# io-board-c-1.net
KiCad netlist of a schematic drawn in EAGLE
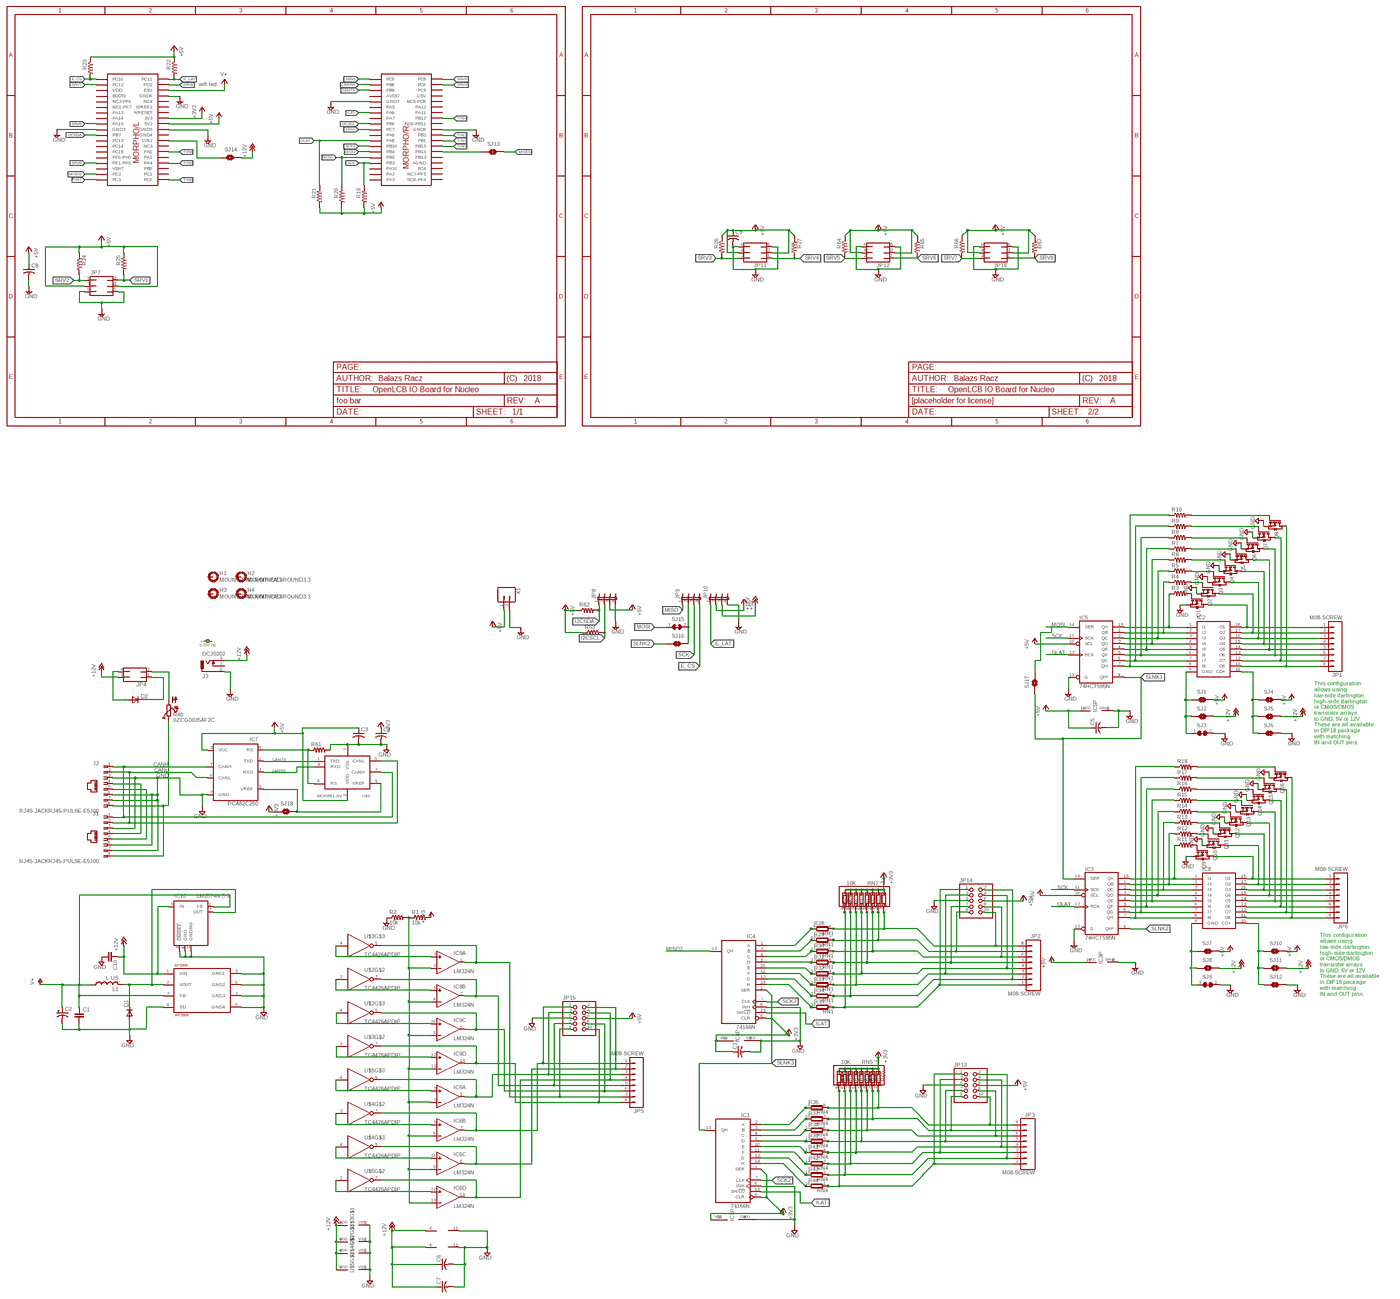
[diagram p0: schematic, sheet 1, overview]
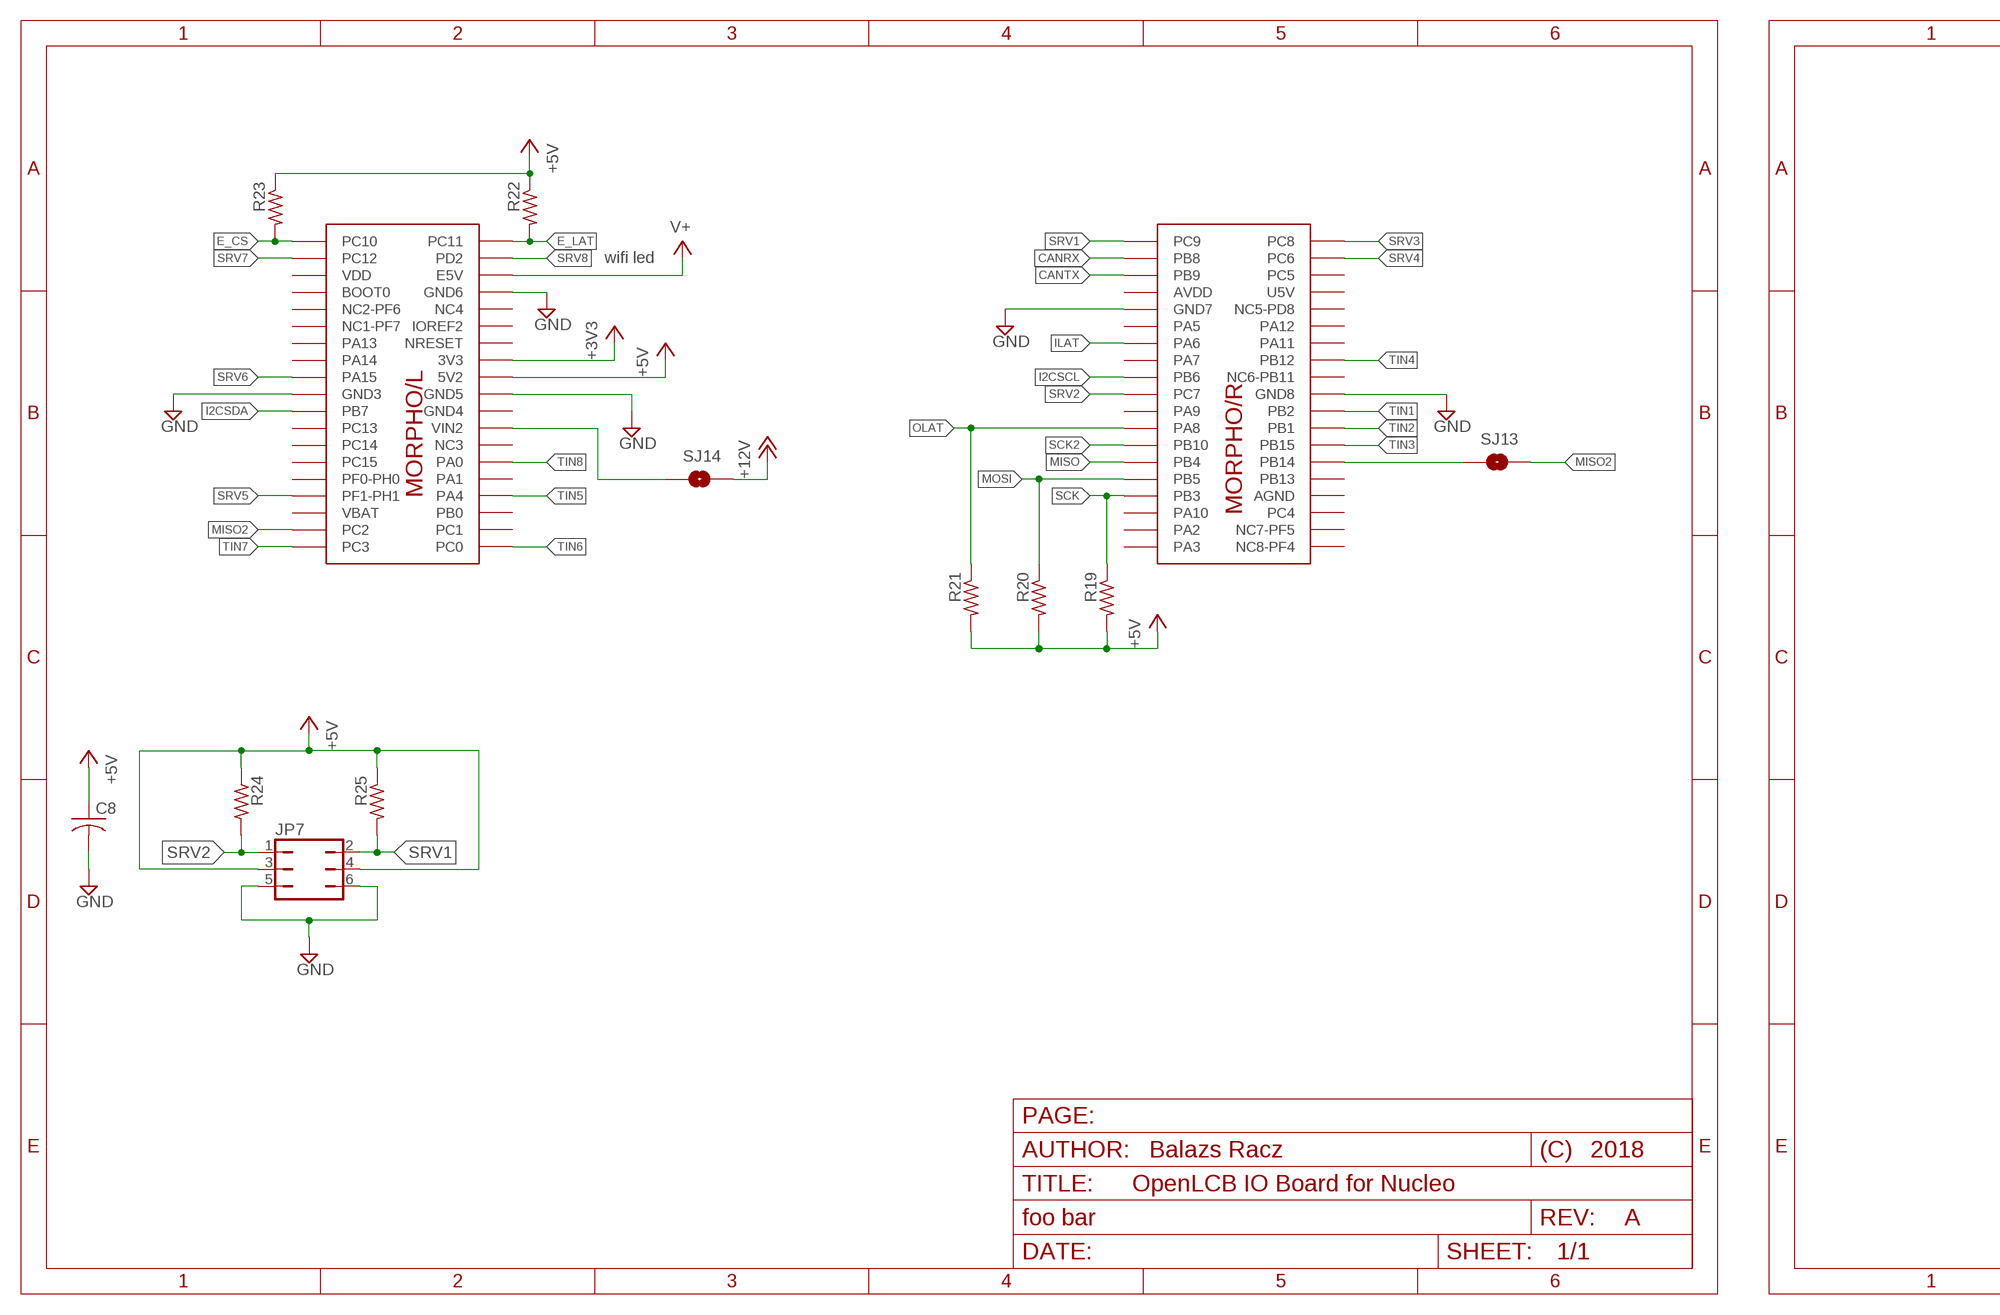
[diagram p1: schematic, sheet 1, part 1 of 4]
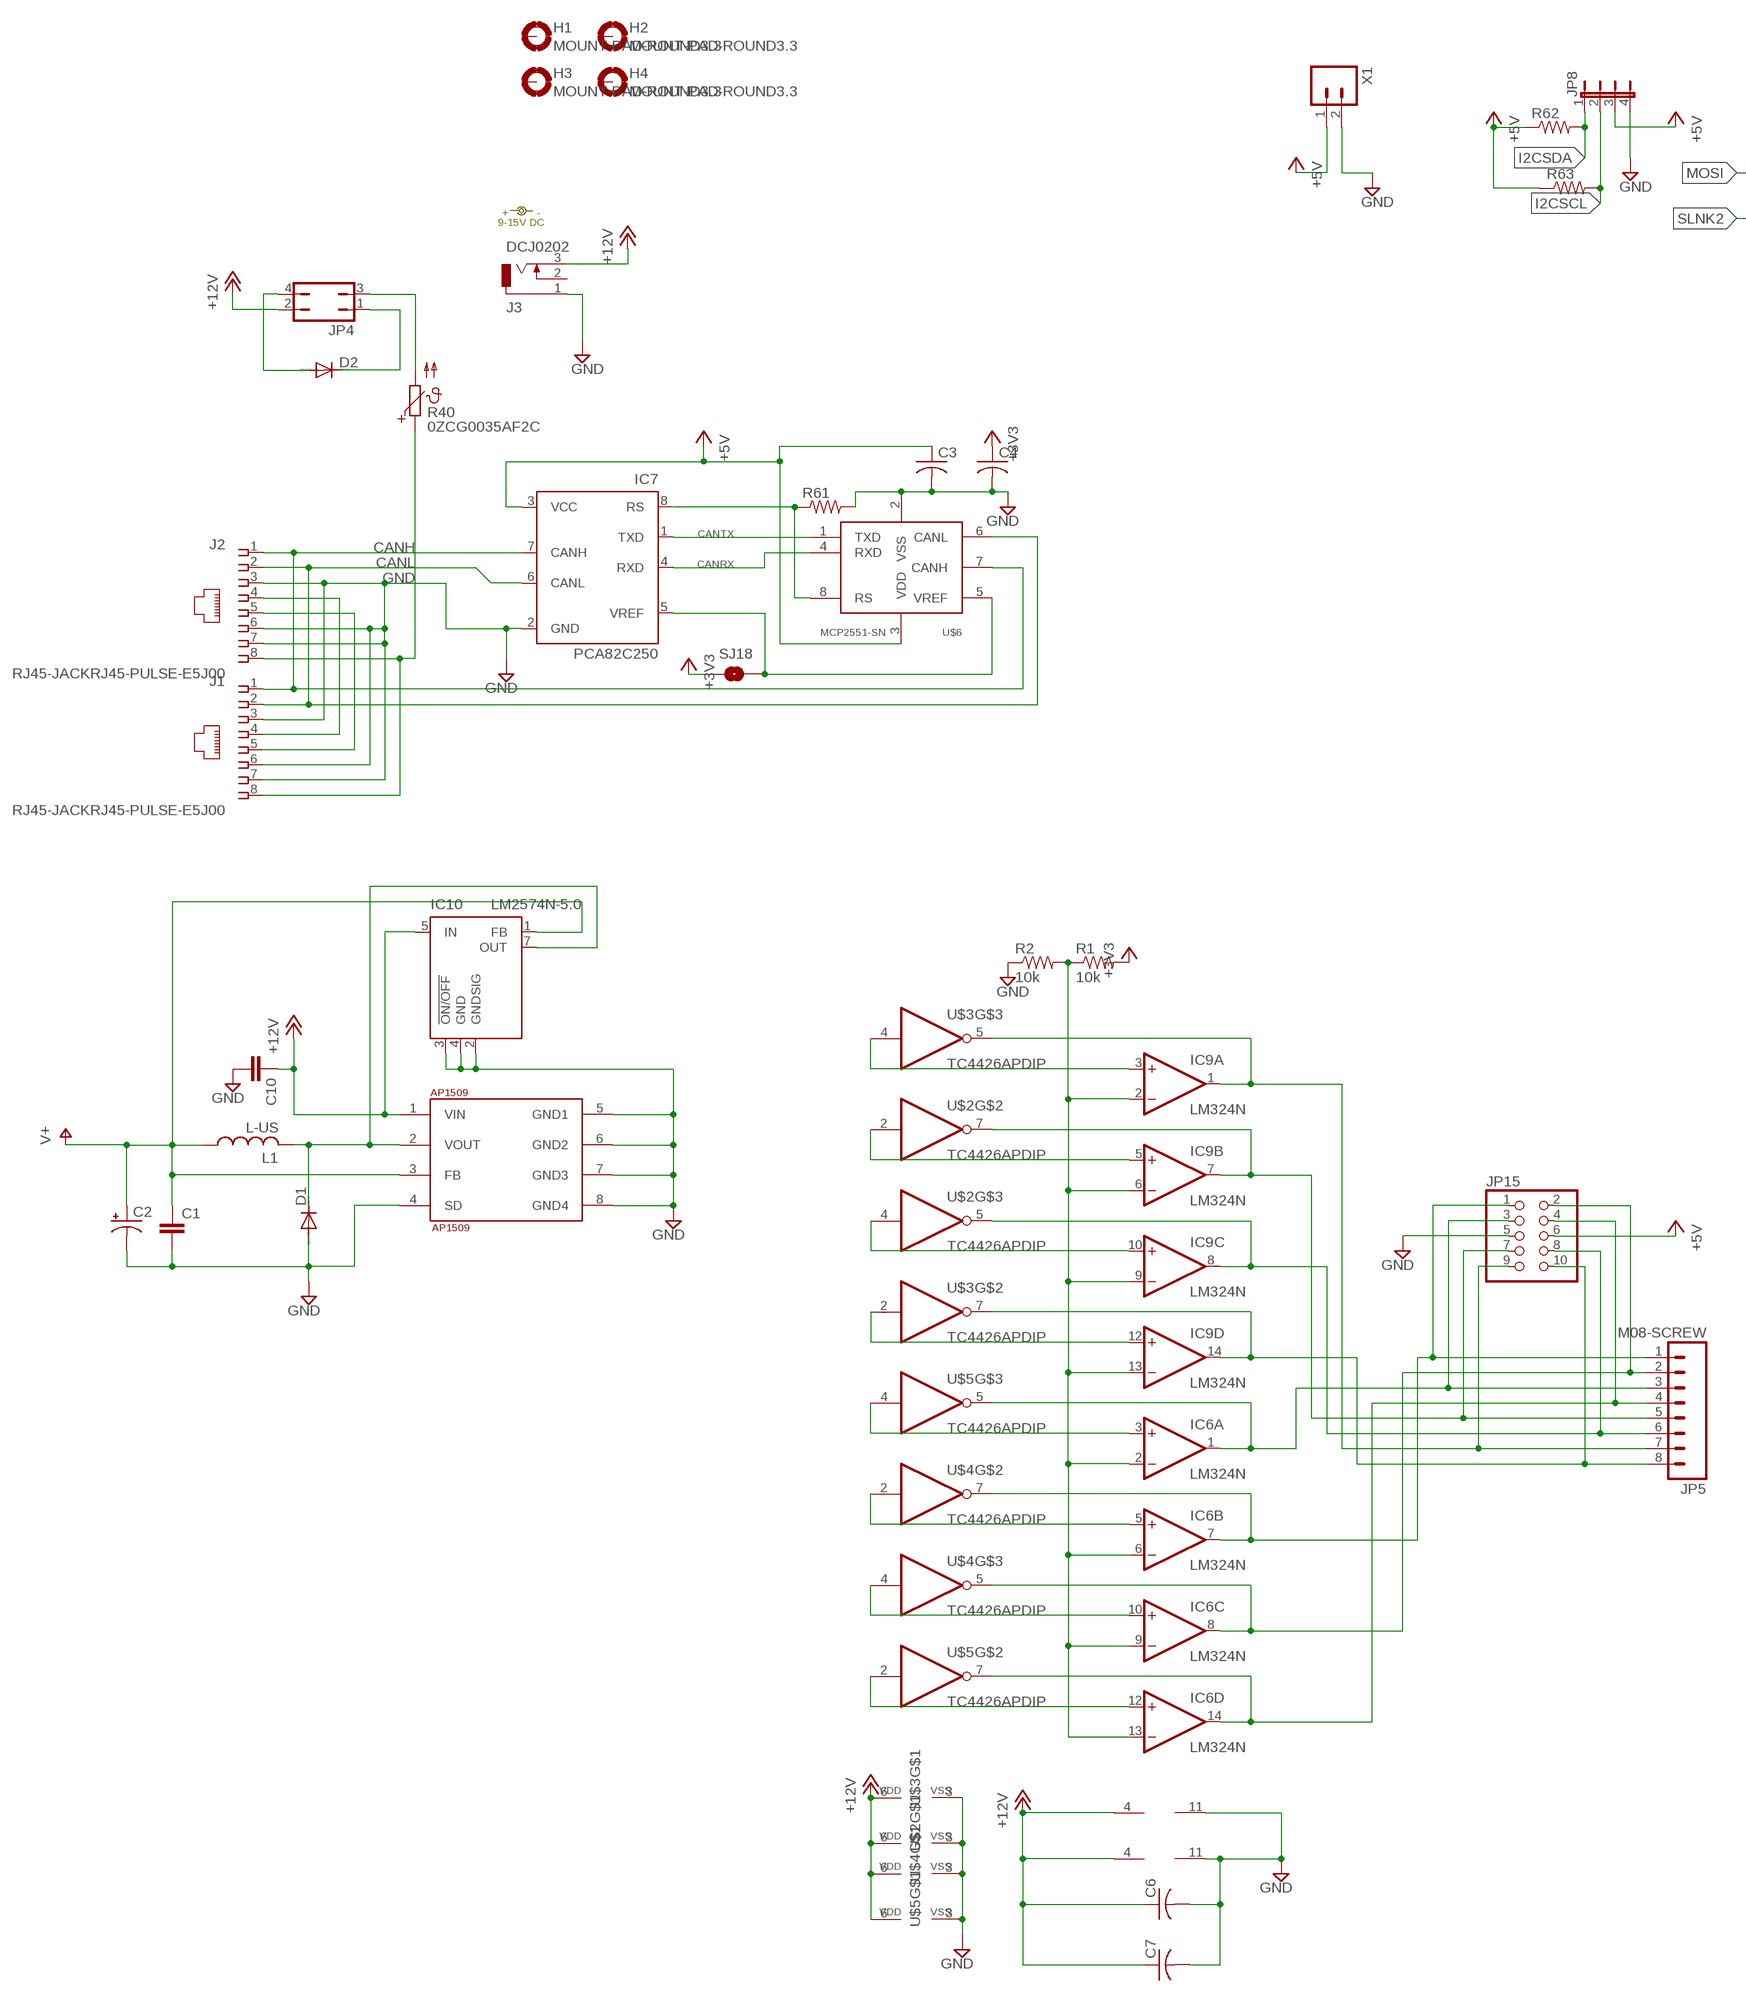
[diagram p2: schematic, sheet 1, part 2 of 4]
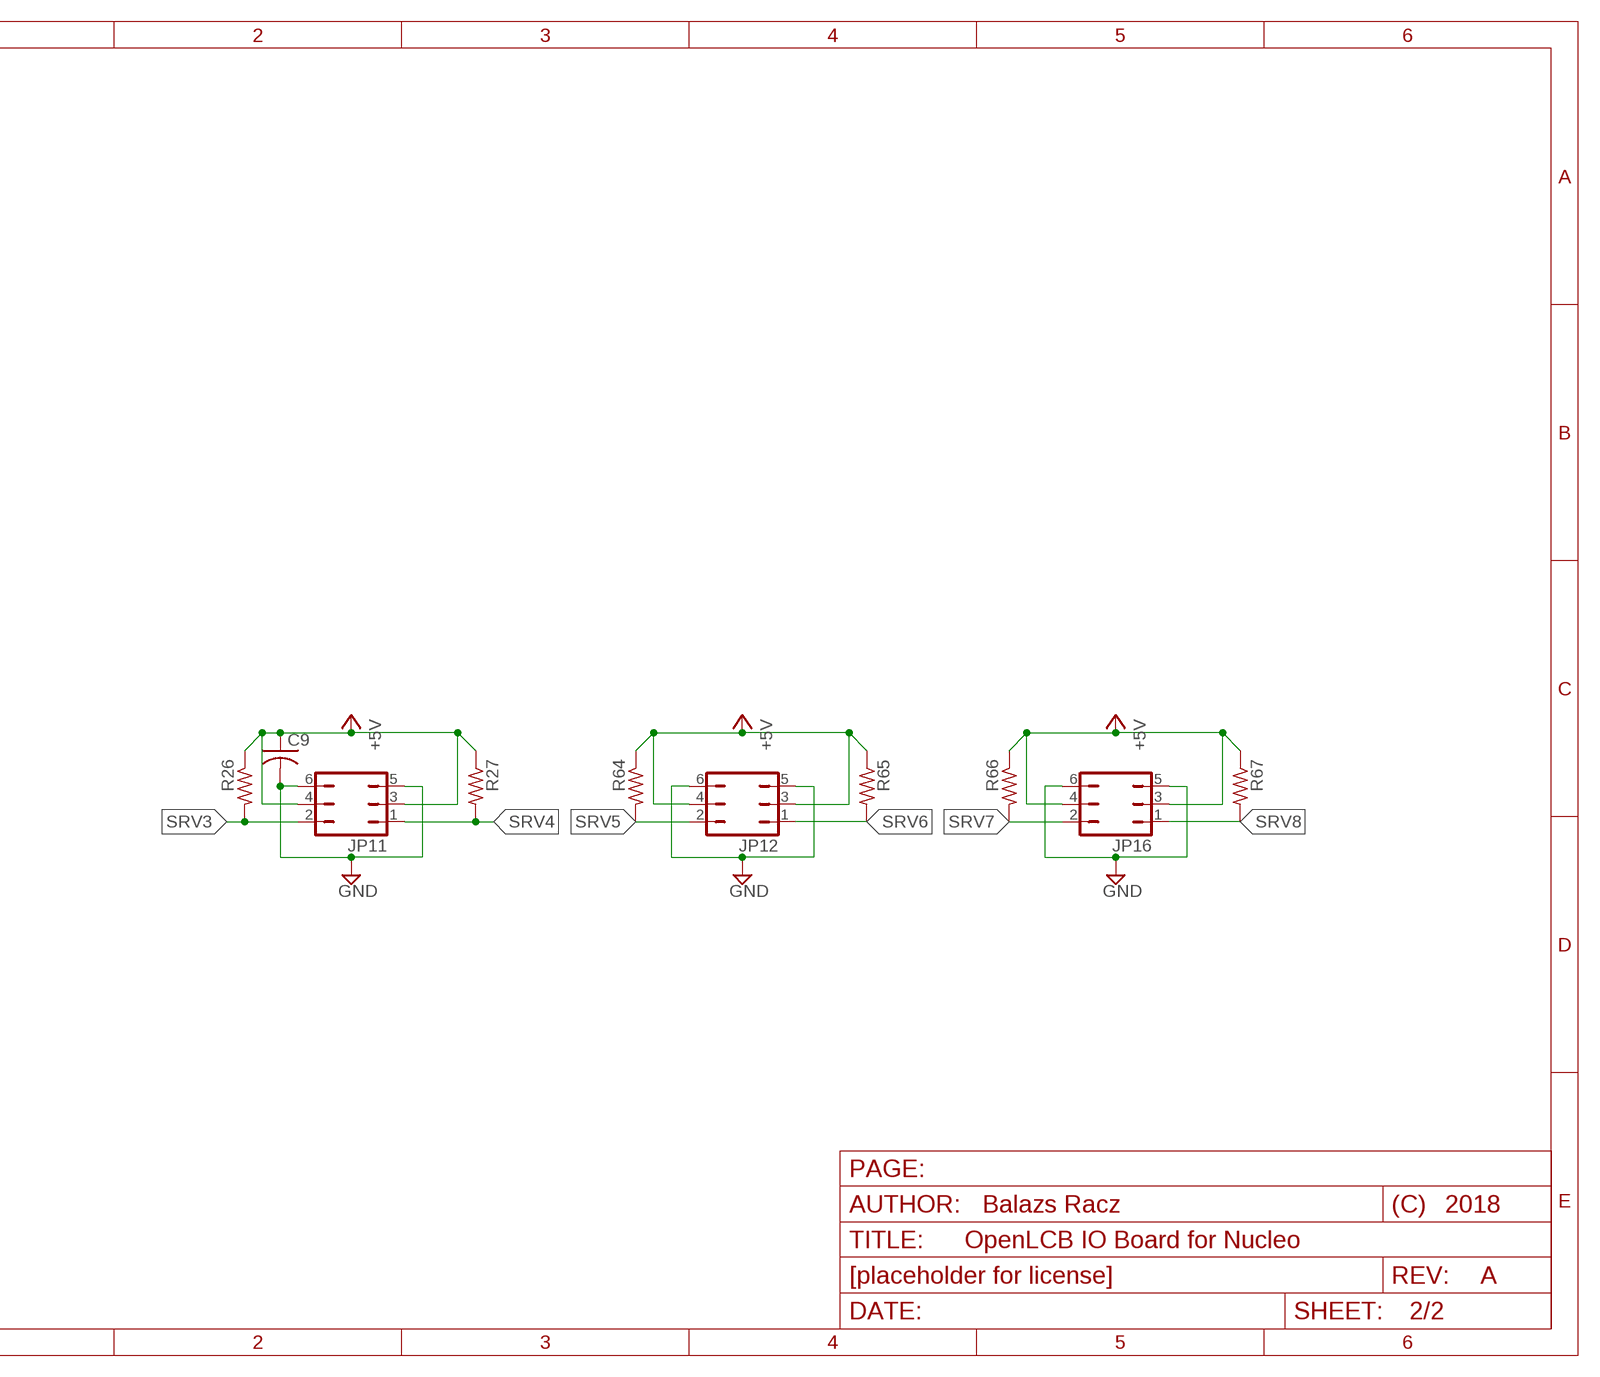
[diagram p3: schematic, sheet 1, part 3 of 4]
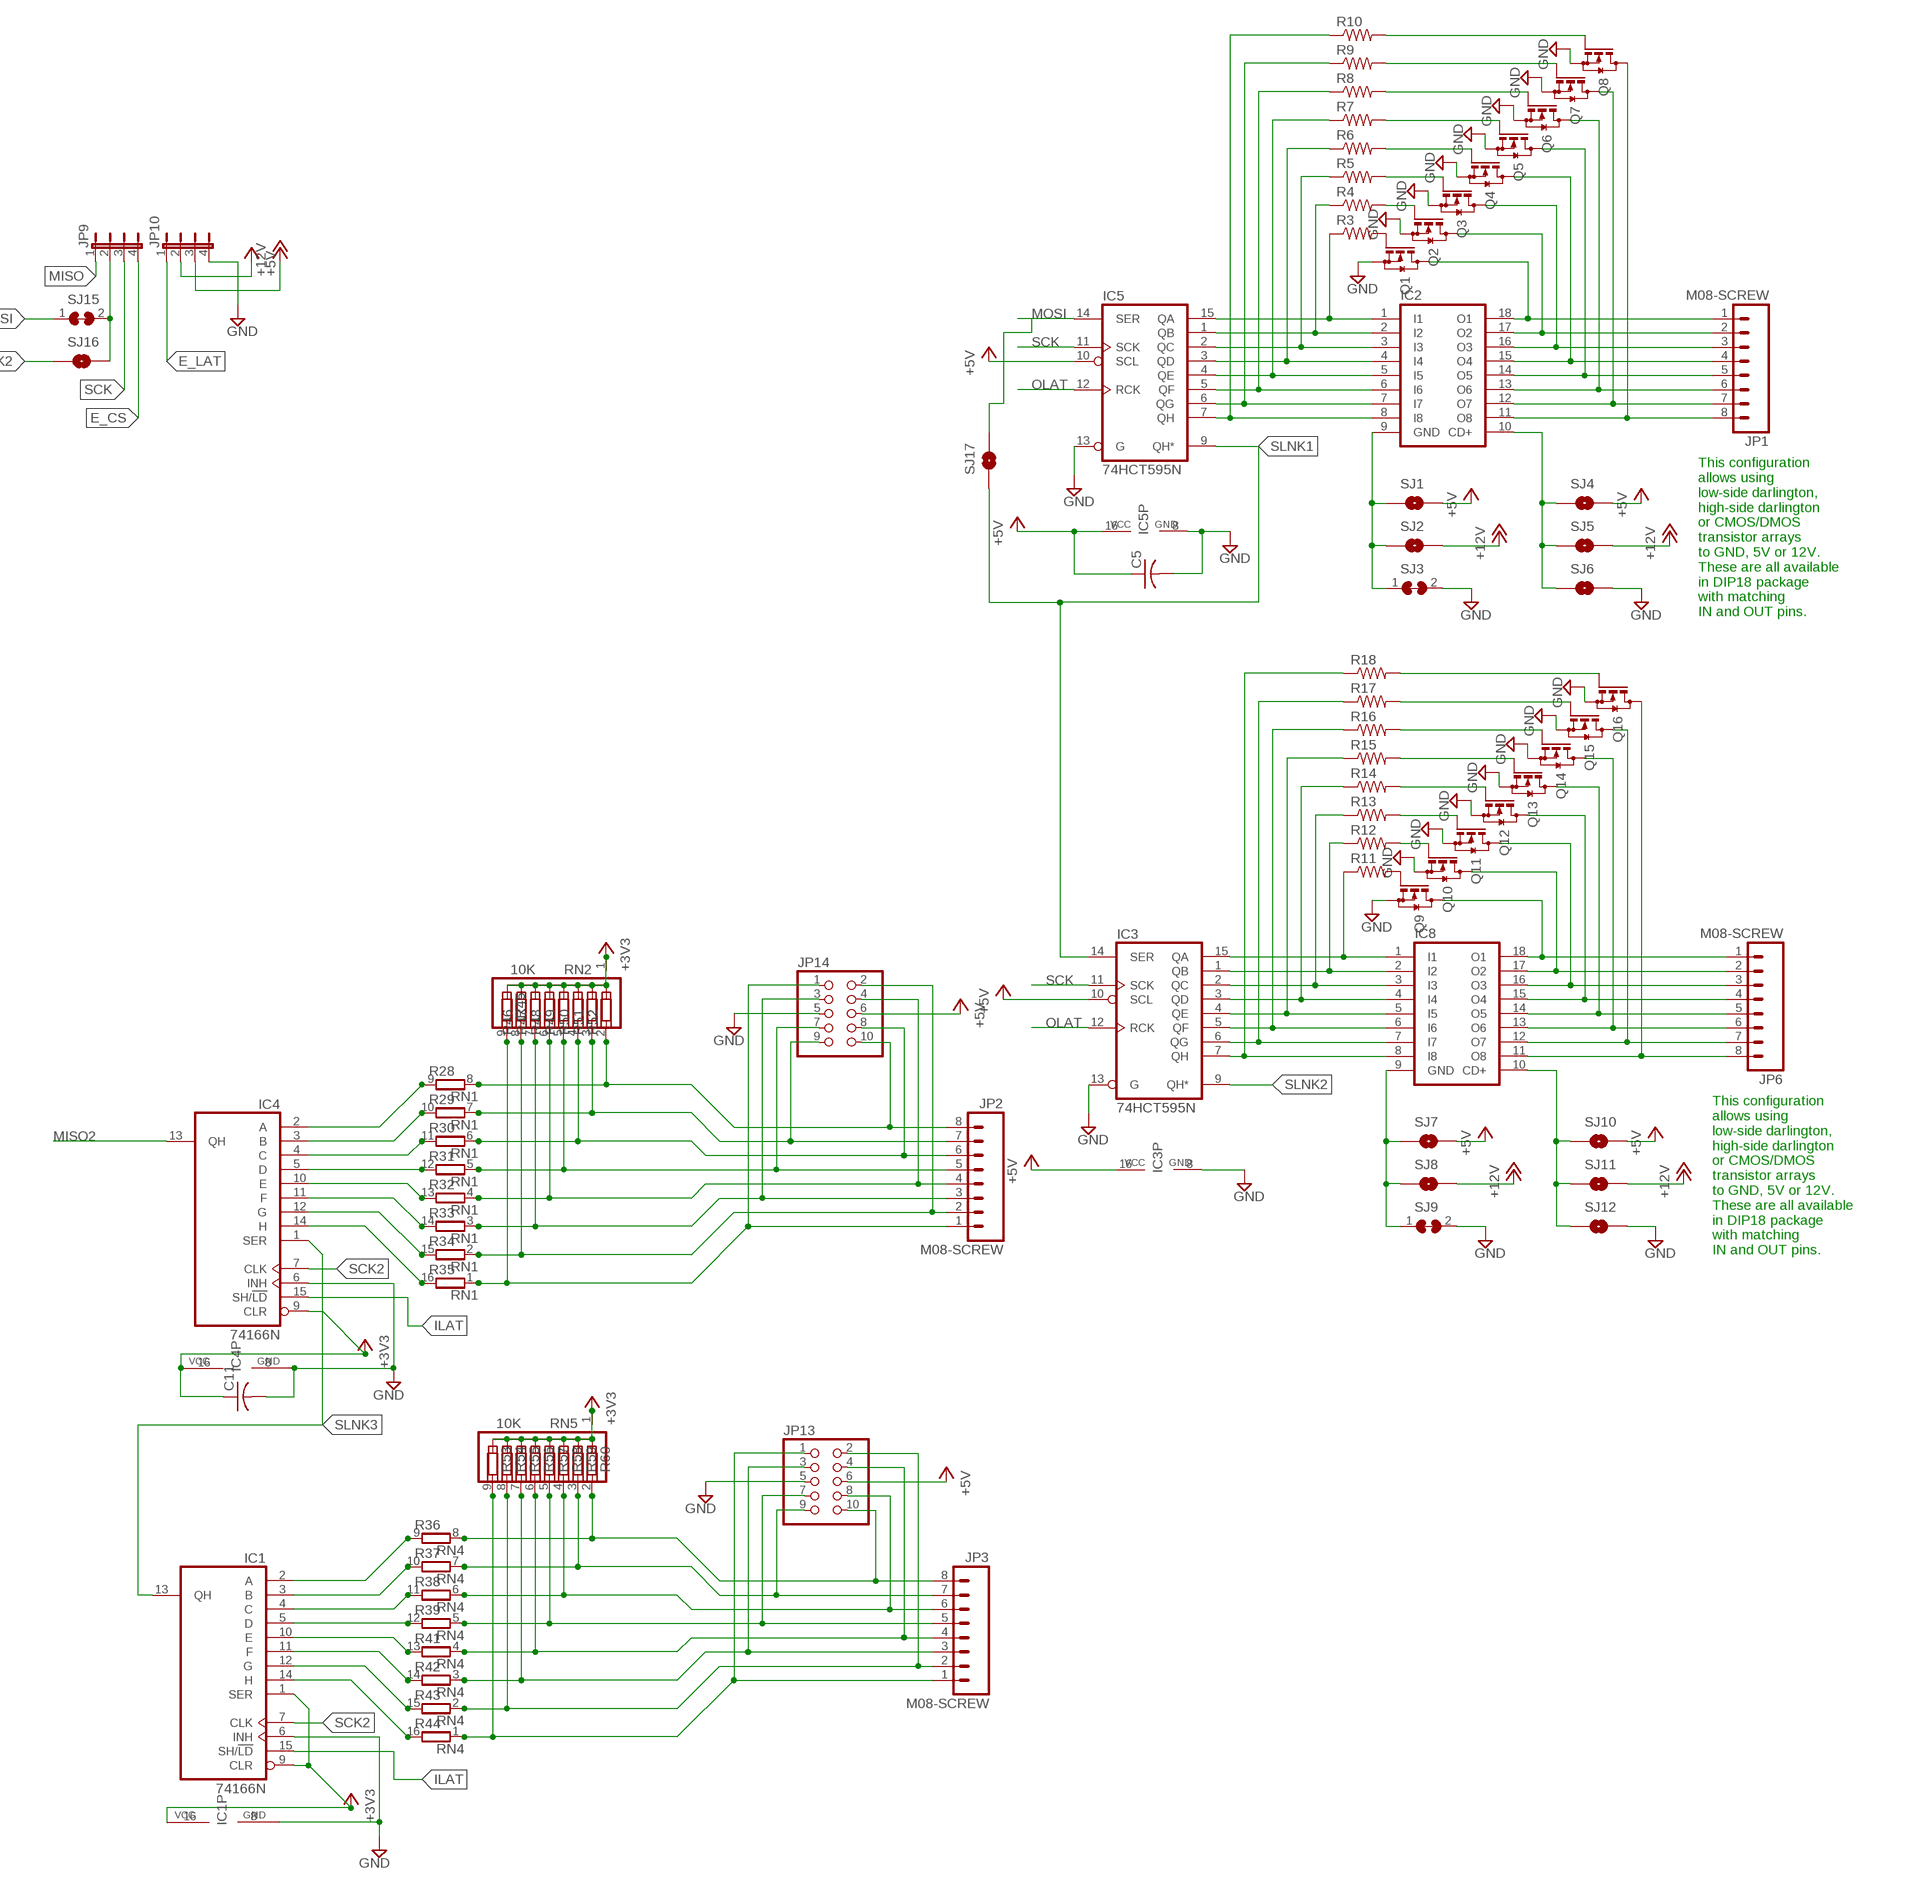
[diagram p4: schematic, sheet 1, part 4 of 4]

(export (version "E")
  (design (tool "Eeschema 10.0.6"))
  (components
    (comp (ref "+12V")
      (value "9-15V DC")
      (footprint "eagle-import:POWER_USAGE")
      (libsource (lib "eagle-import") (part "DOC-POWER_LABEL"))
    )
    (comp (ref "AP1509")
      (value "AP1509")
      (footprint "eagle-import:SO-08")
      (libsource (lib "eagle-import") (part "AP1509"))
    )
    (comp (ref "C1")
      (value "C-EUC1206")
      (footprint "eagle-import:C1206")
      (libsource (lib "eagle-import") (part "C-EUC1206"))
    )
    (comp (ref "C2")
      (value "CPOL-USE2.5-5")
      (footprint "eagle-import:E2,5-5")
      (libsource (lib "eagle-import") (part "CPOL-USE2.5-5"))
    )
    (comp (ref "C3")
      (value "C-USC0805")
      (footprint "eagle-import:C0805")
      (libsource (lib "eagle-import") (part "C-USC0805"))
    )
    (comp (ref "C4")
      (value "C-USC0805")
      (footprint "eagle-import:C0805")
      (libsource (lib "eagle-import") (part "C-USC0805"))
    )
    (comp (ref "C5")
      (value "C-USC0805")
      (footprint "eagle-import:C0805")
      (libsource (lib "eagle-import") (part "C-USC0805"))
    )
    (comp (ref "C6")
      (value "C-USC1206")
      (footprint "eagle-import:C1206")
      (libsource (lib "eagle-import") (part "C-USC1206"))
    )
    (comp (ref "C7")
      (value "C-USC1206")
      (footprint "eagle-import:C1206")
      (libsource (lib "eagle-import") (part "C-USC1206"))
    )
    (comp (ref "C8")
      (value "C-USC1206")
      (footprint "eagle-import:C1206")
      (libsource (lib "eagle-import") (part "C-USC1206"))
    )
    (comp (ref "C9")
      (value "C-USC1206")
      (footprint "eagle-import:C1206")
      (libsource (lib "eagle-import") (part "C-USC1206"))
    )
    (comp (ref "C10")
      (value "C-EUC1206")
      (footprint "eagle-import:C1206")
      (libsource (lib "eagle-import") (part "C-EUC1206"))
    )
    (comp (ref "C11")
      (value "C-USC0805")
      (footprint "eagle-import:C0805")
      (libsource (lib "eagle-import") (part "C-USC0805"))
    )
    (comp (ref "D1")
      (value "DIODE-DO41-7.6")
      (footprint "eagle-import:DO41-7.6")
      (libsource (lib "eagle-import") (part "DIODE-DO41-7.6"))
    )
    (comp (ref "D2")
      (value "DIODE-DO41-7.6")
      (footprint "eagle-import:DO41-7.6")
      (libsource (lib "eagle-import") (part "DIODE-DO41-7.6"))
    )
    (comp (ref "H1")
      (value "MOUNT-PAD-ROUND3.3")
      (footprint "eagle-import:3,3-PAD")
      (libsource (lib "eagle-import") (part "MOUNT-PAD-ROUND3.3"))
    )
    (comp (ref "H2")
      (value "MOUNT-PAD-ROUND3.3")
      (footprint "eagle-import:3,3-PAD")
      (libsource (lib "eagle-import") (part "MOUNT-PAD-ROUND3.3"))
    )
    (comp (ref "H3")
      (value "MOUNT-PAD-ROUND3.3")
      (footprint "eagle-import:3,3-PAD")
      (libsource (lib "eagle-import") (part "MOUNT-PAD-ROUND3.3"))
    )
    (comp (ref "H4")
      (value "MOUNT-PAD-ROUND3.3")
      (footprint "eagle-import:3,3-PAD")
      (libsource (lib "eagle-import") (part "MOUNT-PAD-ROUND3.3"))
    )
    (comp (ref "IC1")
      (value "74166N")
      (footprint "eagle-import:DIL16")
      (libsource (lib "eagle-import") (part "74166N"))
    )
    (comp (ref "IC2")
      (value "ULN2803A")
      (footprint "eagle-import:DIL18-THIN")
      (libsource (lib "eagle-import") (part "ULN2803A"))
    )
    (comp (ref "IC3")
      (value "74HCT595N")
      (footprint "eagle-import:DIL16")
      (libsource (lib "eagle-import") (part "74595NHCT"))
    )
    (comp (ref "IC4")
      (value "74166N")
      (footprint "eagle-import:DIL16")
      (libsource (lib "eagle-import") (part "74166N"))
    )
    (comp (ref "IC5")
      (value "74HCT595N")
      (footprint "eagle-import:DIL16")
      (libsource (lib "eagle-import") (part "74595NHCT"))
    )
    (comp (ref "IC6")
      (value "LM324N")
      (footprint "eagle-import:DIL14")
      (libsource (lib "eagle-import") (part "LM324N"))
    )
    (comp (ref "IC7")
      (value "PCA82C250")
      (footprint "eagle-import:DIL08")
      (libsource (lib "eagle-import") (part "PCA82C250"))
    )
    (comp (ref "IC8")
      (value "ULN2803A")
      (footprint "eagle-import:DIL18-THIN")
      (libsource (lib "eagle-import") (part "ULN2803A"))
    )
    (comp (ref "IC9")
      (value "LM324N")
      (footprint "eagle-import:DIL14")
      (libsource (lib "eagle-import") (part "LM324N"))
    )
    (comp (ref "IC10")
      (value "LM2574N-5.0")
      (footprint "eagle-import:DIL08")
      (libsource (lib "eagle-import") (part "LM2574?-N5.0"))
    )
    (comp (ref "J1")
      (value "RJ45-JACKRJ45-PULSE-E5J00")
      (footprint "eagle-import:RJ45-PULSE-E5J88")
      (libsource (lib "eagle-import") (part "RJ45-JACKRJ45-PULSE-E5J00"))
    )
    (comp (ref "J2")
      (value "RJ45-JACKRJ45-PULSE-E5J00")
      (footprint "eagle-import:RJ45-PULSE-E5J88")
      (libsource (lib "eagle-import") (part "RJ45-JACKRJ45-PULSE-E5J00"))
    )
    (comp (ref "J3")
      (value "DCJ0202")
      (footprint "eagle-import:DCJ0202")
      (libsource (lib "eagle-import") (part "DCJ0202"))
    )
    (comp (ref "JP1")
      (value "M08-SCREW")
      (footprint "eagle-import:1X08_TERMINAL")
      (libsource (lib "eagle-import") (part "M08-SCREW"))
    )
    (comp (ref "JP2")
      (value "M08-SCREW")
      (footprint "eagle-import:1X08_TERMINAL")
      (libsource (lib "eagle-import") (part "M08-SCREW"))
    )
    (comp (ref "JP3")
      (value "M08-SCREW")
      (footprint "eagle-import:1X08_TERMINAL")
      (libsource (lib "eagle-import") (part "M08-SCREW"))
    )
    (comp (ref "JP4")
      (value "JP2Q")
      (footprint "eagle-import:JP2Q")
      (libsource (lib "eagle-import") (part "JP2Q"))
    )
    (comp (ref "JP5")
      (value "M08-SCREW")
      (footprint "eagle-import:1X08_TERMINAL")
      (libsource (lib "eagle-import") (part "M08-SCREW"))
    )
    (comp (ref "JP6")
      (value "M08-SCREW")
      (footprint "eagle-import:1X08_TERMINAL")
      (libsource (lib "eagle-import") (part "M08-SCREW"))
    )
    (comp (ref "JP7")
      (value "JP3Q")
      (footprint "eagle-import:JP3Q")
      (libsource (lib "eagle-import") (part "JP3Q"))
    )
    (comp (ref "JP8")
      (value "JP4-FLAT")
      (footprint "eagle-import:JP4F")
      (libsource (lib "eagle-import") (part "JP4-FLAT"))
    )
    (comp (ref "JP9")
      (value "JP4-FLAT")
      (footprint "eagle-import:JP4F")
      (libsource (lib "eagle-import") (part "JP4-FLAT"))
    )
    (comp (ref "JP10")
      (value "JP4-FLAT")
      (footprint "eagle-import:JP4F")
      (libsource (lib "eagle-import") (part "JP4-FLAT"))
    )
    (comp (ref "JP11")
      (value "JP3Q")
      (footprint "eagle-import:JP3Q")
      (libsource (lib "eagle-import") (part "JP3Q"))
    )
    (comp (ref "JP12")
      (value "JP3Q")
      (footprint "eagle-import:JP3Q")
      (libsource (lib "eagle-import") (part "JP3Q"))
    )
    (comp (ref "JP13")
      (value "PINHD-2X5CN")
      (footprint "eagle-import:CON10M")
      (libsource (lib "eagle-import") (part "PINHD-2X5CN"))
    )
    (comp (ref "JP14")
      (value "PINHD-2X5CN")
      (footprint "eagle-import:CON10M")
      (libsource (lib "eagle-import") (part "PINHD-2X5CN"))
    )
    (comp (ref "JP15")
      (value "PINHD-2X5CN")
      (footprint "eagle-import:CON10M")
      (libsource (lib "eagle-import") (part "PINHD-2X5CN"))
    )
    (comp (ref "JP16")
      (value "JP3Q")
      (footprint "eagle-import:JP3Q")
      (libsource (lib "eagle-import") (part "JP3Q"))
    )
    (comp (ref "L1")
      (value "L-US")
      (footprint "eagle-import:L5-8,5")
      (libsource (lib "eagle-import") (part "L-US"))
    )
    (comp (ref "Q1")
      (value "BSS123")
      (footprint "eagle-import:SOT23")
      (libsource (lib "eagle-import") (part "BSS123"))
    )
    (comp (ref "Q2")
      (value "BSS123")
      (footprint "eagle-import:SOT23")
      (libsource (lib "eagle-import") (part "BSS123"))
    )
    (comp (ref "Q3")
      (value "BSS123")
      (footprint "eagle-import:SOT23")
      (libsource (lib "eagle-import") (part "BSS123"))
    )
    (comp (ref "Q4")
      (value "BSS123")
      (footprint "eagle-import:SOT23")
      (libsource (lib "eagle-import") (part "BSS123"))
    )
    (comp (ref "Q5")
      (value "BSS123")
      (footprint "eagle-import:SOT23")
      (libsource (lib "eagle-import") (part "BSS123"))
    )
    (comp (ref "Q6")
      (value "BSS123")
      (footprint "eagle-import:SOT23")
      (libsource (lib "eagle-import") (part "BSS123"))
    )
    (comp (ref "Q7")
      (value "BSS123")
      (footprint "eagle-import:SOT23")
      (libsource (lib "eagle-import") (part "BSS123"))
    )
    (comp (ref "Q8")
      (value "BSS123")
      (footprint "eagle-import:SOT23")
      (libsource (lib "eagle-import") (part "BSS123"))
    )
    (comp (ref "Q9")
      (value "BSS123")
      (footprint "eagle-import:SOT23")
      (libsource (lib "eagle-import") (part "BSS123"))
    )
    (comp (ref "Q10")
      (value "BSS123")
      (footprint "eagle-import:SOT23")
      (libsource (lib "eagle-import") (part "BSS123"))
    )
    (comp (ref "Q11")
      (value "BSS123")
      (footprint "eagle-import:SOT23")
      (libsource (lib "eagle-import") (part "BSS123"))
    )
    (comp (ref "Q12")
      (value "BSS123")
      (footprint "eagle-import:SOT23")
      (libsource (lib "eagle-import") (part "BSS123"))
    )
    (comp (ref "Q13")
      (value "BSS123")
      (footprint "eagle-import:SOT23")
      (libsource (lib "eagle-import") (part "BSS123"))
    )
    (comp (ref "Q14")
      (value "BSS123")
      (footprint "eagle-import:SOT23")
      (libsource (lib "eagle-import") (part "BSS123"))
    )
    (comp (ref "Q15")
      (value "BSS123")
      (footprint "eagle-import:SOT23")
      (libsource (lib "eagle-import") (part "BSS123"))
    )
    (comp (ref "Q16")
      (value "BSS123")
      (footprint "eagle-import:SOT23")
      (libsource (lib "eagle-import") (part "BSS123"))
    )
    (comp (ref "R1")
      (value "10k")
      (footprint "eagle-import:R0805")
      (libsource (lib "eagle-import") (part "R-US_R0805"))
    )
    (comp (ref "R2")
      (value "10k")
      (footprint "eagle-import:R0805")
      (libsource (lib "eagle-import") (part "R-US_R0805"))
    )
    (comp (ref "R3")
      (value "R-US_R0603")
      (footprint "eagle-import:R0603")
      (libsource (lib "eagle-import") (part "R-US_R0603"))
    )
    (comp (ref "R4")
      (value "R-US_R0603")
      (footprint "eagle-import:R0603")
      (libsource (lib "eagle-import") (part "R-US_R0603"))
    )
    (comp (ref "R5")
      (value "R-US_R0603")
      (footprint "eagle-import:R0603")
      (libsource (lib "eagle-import") (part "R-US_R0603"))
    )
    (comp (ref "R6")
      (value "R-US_R0603")
      (footprint "eagle-import:R0603")
      (libsource (lib "eagle-import") (part "R-US_R0603"))
    )
    (comp (ref "R7")
      (value "R-US_R0603")
      (footprint "eagle-import:R0603")
      (libsource (lib "eagle-import") (part "R-US_R0603"))
    )
    (comp (ref "R8")
      (value "R-US_R0603")
      (footprint "eagle-import:R0603")
      (libsource (lib "eagle-import") (part "R-US_R0603"))
    )
    (comp (ref "R9")
      (value "R-US_R0603")
      (footprint "eagle-import:R0603")
      (libsource (lib "eagle-import") (part "R-US_R0603"))
    )
    (comp (ref "R10")
      (value "R-US_R0603")
      (footprint "eagle-import:R0603")
      (libsource (lib "eagle-import") (part "R-US_R0603"))
    )
    (comp (ref "R11")
      (value "R-US_R0603")
      (footprint "eagle-import:R0603")
      (libsource (lib "eagle-import") (part "R-US_R0603"))
    )
    (comp (ref "R12")
      (value "R-US_R0603")
      (footprint "eagle-import:R0603")
      (libsource (lib "eagle-import") (part "R-US_R0603"))
    )
    (comp (ref "R13")
      (value "R-US_R0603")
      (footprint "eagle-import:R0603")
      (libsource (lib "eagle-import") (part "R-US_R0603"))
    )
    (comp (ref "R14")
      (value "R-US_R0603")
      (footprint "eagle-import:R0603")
      (libsource (lib "eagle-import") (part "R-US_R0603"))
    )
    (comp (ref "R15")
      (value "R-US_R0603")
      (footprint "eagle-import:R0603")
      (libsource (lib "eagle-import") (part "R-US_R0603"))
    )
    (comp (ref "R16")
      (value "R-US_R0603")
      (footprint "eagle-import:R0603")
      (libsource (lib "eagle-import") (part "R-US_R0603"))
    )
    (comp (ref "R17")
      (value "R-US_R0603")
      (footprint "eagle-import:R0603")
      (libsource (lib "eagle-import") (part "R-US_R0603"))
    )
    (comp (ref "R18")
      (value "R-US_R0603")
      (footprint "eagle-import:R0603")
      (libsource (lib "eagle-import") (part "R-US_R0603"))
    )
    (comp (ref "R19")
      (value "R-US_R0805")
      (footprint "eagle-import:R0805")
      (libsource (lib "eagle-import") (part "rcl_334_R-US_R0805"))
    )
    (comp (ref "R20")
      (value "R-US_R0805")
      (footprint "eagle-import:R0805")
      (libsource (lib "eagle-import") (part "rcl_334_R-US_R0805"))
    )
    (comp (ref "R21")
      (value "R-US_R0805")
      (footprint "eagle-import:R0805")
      (libsource (lib "eagle-import") (part "rcl_334_R-US_R0805"))
    )
    (comp (ref "R22")
      (value "R-US_R0805")
      (footprint "eagle-import:R0805")
      (libsource (lib "eagle-import") (part "rcl_334_R-US_R0805"))
    )
    (comp (ref "R23")
      (value "R-US_R0805")
      (footprint "eagle-import:R0805")
      (libsource (lib "eagle-import") (part "rcl_334_R-US_R0805"))
    )
    (comp (ref "R24")
      (value "R-US_R0805")
      (footprint "eagle-import:R0805")
      (libsource (lib "eagle-import") (part "rcl_334_R-US_R0805"))
    )
    (comp (ref "R25")
      (value "R-US_R0805")
      (footprint "eagle-import:R0805")
      (libsource (lib "eagle-import") (part "rcl_334_R-US_R0805"))
    )
    (comp (ref "R26")
      (value "R-US_R0805")
      (footprint "eagle-import:R0805")
      (libsource (lib "eagle-import") (part "rcl_334_R-US_R0805"))
    )
    (comp (ref "R27")
      (value "R-US_R0805")
      (footprint "eagle-import:R0805")
      (libsource (lib "eagle-import") (part "rcl_334_R-US_R0805"))
    )
    (comp (ref "R28")
      (value "R-EU_R0603")
      (footprint "eagle-import:R0603")
      (libsource (lib "eagle-import") (part "R-EU_R0603"))
    )
    (comp (ref "R29")
      (value "R-EU_R0603")
      (footprint "eagle-import:R0603")
      (libsource (lib "eagle-import") (part "R-EU_R0603"))
    )
    (comp (ref "R30")
      (value "R-EU_R0603")
      (footprint "eagle-import:R0603")
      (libsource (lib "eagle-import") (part "R-EU_R0603"))
    )
    (comp (ref "R31")
      (value "R-EU_R0603")
      (footprint "eagle-import:R0603")
      (libsource (lib "eagle-import") (part "R-EU_R0603"))
    )
    (comp (ref "R32")
      (value "R-EU_R0603")
      (footprint "eagle-import:R0603")
      (libsource (lib "eagle-import") (part "R-EU_R0603"))
    )
    (comp (ref "R33")
      (value "R-EU_R0603")
      (footprint "eagle-import:R0603")
      (libsource (lib "eagle-import") (part "R-EU_R0603"))
    )
    (comp (ref "R34")
      (value "R-EU_R0603")
      (footprint "eagle-import:R0603")
      (libsource (lib "eagle-import") (part "R-EU_R0603"))
    )
    (comp (ref "R35")
      (value "R-EU_R0603")
      (footprint "eagle-import:R0603")
      (libsource (lib "eagle-import") (part "R-EU_R0603"))
    )
    (comp (ref "R36")
      (value "R-EU_R0603")
      (footprint "eagle-import:R0603")
      (libsource (lib "eagle-import") (part "R-EU_R0603"))
    )
    (comp (ref "R37")
      (value "R-EU_R0603")
      (footprint "eagle-import:R0603")
      (libsource (lib "eagle-import") (part "R-EU_R0603"))
    )
    (comp (ref "R38")
      (value "R-EU_R0603")
      (footprint "eagle-import:R0603")
      (libsource (lib "eagle-import") (part "R-EU_R0603"))
    )
    (comp (ref "R39")
      (value "R-EU_R0603")
      (footprint "eagle-import:R0603")
      (libsource (lib "eagle-import") (part "R-EU_R0603"))
    )
    (comp (ref "R40")
      (value "0ZCG0035AF2C")
      (footprint "eagle-import:PTC1812")
      (libsource (lib "eagle-import") (part "PTC_1812"))
    )
    (comp (ref "R41")
      (value "R-EU_R0603")
      (footprint "eagle-import:R0603")
      (libsource (lib "eagle-import") (part "R-EU_R0603"))
    )
    (comp (ref "R42")
      (value "R-EU_R0603")
      (footprint "eagle-import:R0603")
      (libsource (lib "eagle-import") (part "R-EU_R0603"))
    )
    (comp (ref "R43")
      (value "R-EU_R0603")
      (footprint "eagle-import:R0603")
      (libsource (lib "eagle-import") (part "R-EU_R0603"))
    )
    (comp (ref "R44")
      (value "R-EU_R0603")
      (footprint "eagle-import:R0603")
      (libsource (lib "eagle-import") (part "R-EU_R0603"))
    )
    (comp (ref "R45")
      (value "R-EU_R0603")
      (footprint "eagle-import:R0603")
      (libsource (lib "eagle-import") (part "R-EU_R0603"))
    )
    (comp (ref "R46")
      (value "R-EU_R0603")
      (footprint "eagle-import:R0603")
      (libsource (lib "eagle-import") (part "R-EU_R0603"))
    )
    (comp (ref "R47")
      (value "R-EU_R0603")
      (footprint "eagle-import:R0603")
      (libsource (lib "eagle-import") (part "R-EU_R0603"))
    )
    (comp (ref "R48")
      (value "R-EU_R0603")
      (footprint "eagle-import:R0603")
      (libsource (lib "eagle-import") (part "R-EU_R0603"))
    )
    (comp (ref "R49")
      (value "R-EU_R0603")
      (footprint "eagle-import:R0603")
      (libsource (lib "eagle-import") (part "R-EU_R0603"))
    )
    (comp (ref "R50")
      (value "R-EU_R0603")
      (footprint "eagle-import:R0603")
      (libsource (lib "eagle-import") (part "R-EU_R0603"))
    )
    (comp (ref "R51")
      (value "R-EU_R0603")
      (footprint "eagle-import:R0603")
      (libsource (lib "eagle-import") (part "R-EU_R0603"))
    )
    (comp (ref "R52")
      (value "R-EU_R0603")
      (footprint "eagle-import:R0603")
      (libsource (lib "eagle-import") (part "R-EU_R0603"))
    )
    (comp (ref "R53")
      (value "R-EU_R0603")
      (footprint "eagle-import:R0603")
      (libsource (lib "eagle-import") (part "R-EU_R0603"))
    )
    (comp (ref "R54")
      (value "R-EU_R0603")
      (footprint "eagle-import:R0603")
      (libsource (lib "eagle-import") (part "R-EU_R0603"))
    )
    (comp (ref "R55")
      (value "R-EU_R0603")
      (footprint "eagle-import:R0603")
      (libsource (lib "eagle-import") (part "R-EU_R0603"))
    )
    (comp (ref "R56")
      (value "R-EU_R0603")
      (footprint "eagle-import:R0603")
      (libsource (lib "eagle-import") (part "R-EU_R0603"))
    )
    (comp (ref "R57")
      (value "R-EU_R0603")
      (footprint "eagle-import:R0603")
      (libsource (lib "eagle-import") (part "R-EU_R0603"))
    )
    (comp (ref "R58")
      (value "R-EU_R0603")
      (footprint "eagle-import:R0603")
      (libsource (lib "eagle-import") (part "R-EU_R0603"))
    )
    (comp (ref "R59")
      (value "R-EU_R0603")
      (footprint "eagle-import:R0603")
      (libsource (lib "eagle-import") (part "R-EU_R0603"))
    )
    (comp (ref "R60")
      (value "R-EU_R0603")
      (footprint "eagle-import:R0603")
      (libsource (lib "eagle-import") (part "R-EU_R0603"))
    )
    (comp (ref "R61")
      (value "R-US_R0805")
      (footprint "eagle-import:R0805")
      (libsource (lib "eagle-import") (part "rcl_334_R-US_R0805"))
    )
    (comp (ref "R62")
      (value "R-US_R0805")
      (footprint "eagle-import:R0805")
      (libsource (lib "eagle-import") (part "rcl_334_R-US_R0805"))
    )
    (comp (ref "R63")
      (value "R-US_R0805")
      (footprint "eagle-import:R0805")
      (libsource (lib "eagle-import") (part "rcl_334_R-US_R0805"))
    )
    (comp (ref "R64")
      (value "R-US_R0805")
      (footprint "eagle-import:R0805")
      (libsource (lib "eagle-import") (part "rcl_334_R-US_R0805"))
    )
    (comp (ref "R65")
      (value "R-US_R0805")
      (footprint "eagle-import:R0805")
      (libsource (lib "eagle-import") (part "rcl_334_R-US_R0805"))
    )
    (comp (ref "R66")
      (value "R-US_R0805")
      (footprint "eagle-import:R0805")
      (libsource (lib "eagle-import") (part "rcl_334_R-US_R0805"))
    )
    (comp (ref "R67")
      (value "R-US_R0805")
      (footprint "eagle-import:R0805")
      (libsource (lib "eagle-import") (part "rcl_334_R-US_R0805"))
    )
    (comp (ref "RN1")
      (value "8R-P")
      (footprint "eagle-import:DIL16")
      (libsource (lib "eagle-import") (part "8R-P"))
    )
    (comp (ref "RN2")
      (value "10K")
      (footprint "eagle-import:SIL9")
      (libsource (lib "eagle-import") (part "G08R"))
    )
    (comp (ref "RN4")
      (value "8R-P")
      (footprint "eagle-import:DIL16")
      (libsource (lib "eagle-import") (part "8R-P"))
    )
    (comp (ref "RN5")
      (value "10K")
      (footprint "eagle-import:SIL9")
      (libsource (lib "eagle-import") (part "G08R"))
    )
    (comp (ref "SJ1")
      (value "SJRND2")
      (footprint "eagle-import:SJ_RND2")
      (libsource (lib "eagle-import") (part "SJRND2"))
    )
    (comp (ref "SJ2")
      (value "SJRND2")
      (footprint "eagle-import:SJ_RND2")
      (libsource (lib "eagle-import") (part "SJRND2"))
    )
    (comp (ref "SJ3")
      (value "SJ-C")
      (footprint "eagle-import:SJW-C")
      (libsource (lib "eagle-import") (part "SJ-C"))
    )
    (comp (ref "SJ4")
      (value "SJRND2")
      (footprint "eagle-import:SJ_RND2")
      (libsource (lib "eagle-import") (part "SJRND2"))
    )
    (comp (ref "SJ5")
      (value "SJRND2")
      (footprint "eagle-import:SJ_RND2")
      (libsource (lib "eagle-import") (part "SJRND2"))
    )
    (comp (ref "SJ6")
      (value "SJRND2")
      (footprint "eagle-import:SJ_RND2")
      (libsource (lib "eagle-import") (part "SJRND2"))
    )
    (comp (ref "SJ7")
      (value "SJRND2")
      (footprint "eagle-import:SJ_RND2")
      (libsource (lib "eagle-import") (part "SJRND2"))
    )
    (comp (ref "SJ8")
      (value "SJRND2")
      (footprint "eagle-import:SJ_RND2")
      (libsource (lib "eagle-import") (part "SJRND2"))
    )
    (comp (ref "SJ9")
      (value "SJ-C")
      (footprint "eagle-import:SJW-C")
      (libsource (lib "eagle-import") (part "SJ-C"))
    )
    (comp (ref "SJ10")
      (value "SJRND2")
      (footprint "eagle-import:SJ_RND2")
      (libsource (lib "eagle-import") (part "SJRND2"))
    )
    (comp (ref "SJ11")
      (value "SJRND2")
      (footprint "eagle-import:SJ_RND2")
      (libsource (lib "eagle-import") (part "SJRND2"))
    )
    (comp (ref "SJ12")
      (value "SJRND2")
      (footprint "eagle-import:SJ_RND2")
      (libsource (lib "eagle-import") (part "SJRND2"))
    )
    (comp (ref "SJ13")
      (value "SJRND2")
      (footprint "eagle-import:SJ_RND2")
      (libsource (lib "eagle-import") (part "SJRND2"))
    )
    (comp (ref "SJ14")
      (value "SJRND2")
      (footprint "eagle-import:SJ_RND2")
      (libsource (lib "eagle-import") (part "SJRND2"))
    )
    (comp (ref "SJ15")
      (value "SJ-C")
      (footprint "eagle-import:SJW-C")
      (libsource (lib "eagle-import") (part "SJ-C"))
    )
    (comp (ref "SJ16")
      (value "SJRND2")
      (footprint "eagle-import:SJ_RND2")
      (libsource (lib "eagle-import") (part "SJRND2"))
    )
    (comp (ref "SJ17")
      (value "SJRND2")
      (footprint "eagle-import:SJ_RND2")
      (libsource (lib "eagle-import") (part "SJRND2"))
    )
    (comp (ref "SJ18")
      (value "SJRND2")
      (footprint "eagle-import:SJ_RND2")
      (libsource (lib "eagle-import") (part "SJRND2"))
    )
    (comp (ref "U$1")
      (value "NUCLEO_64_GENERIC")
      (footprint "eagle-import:NUCLEO_BRD_BASE64")
      (libsource (lib "eagle-import") (part "NUCLEO_64_GENERIC"))
    )
    (comp (ref "U$2")
      (value "TC4426APDIP")
      (footprint "eagle-import:DIL08-LONG")
      (libsource (lib "eagle-import") (part "TC4426APDIP"))
    )
    (comp (ref "U$3")
      (value "TC4426APDIP")
      (footprint "eagle-import:DIL08-LONG")
      (libsource (lib "eagle-import") (part "TC4426APDIP"))
    )
    (comp (ref "U$4")
      (value "TC4426APDIP")
      (footprint "eagle-import:DIL08-LONG")
      (libsource (lib "eagle-import") (part "TC4426APDIP"))
    )
    (comp (ref "U$5")
      (value "TC4426APDIP")
      (footprint "eagle-import:DIL08-LONG")
      (libsource (lib "eagle-import") (part "TC4426APDIP"))
    )
    (comp (ref "U$6")
      (value "MCP2551-SN")
      (footprint "eagle-import:SO-08")
      (libsource (lib "eagle-import") (part "MCP2551-SN"))
    )
    (comp (ref "X1")
      (value "CONNECTOR-M023.5MM-LOCK")
      (footprint "eagle-import:SCREWTERMINAL-3.5MM-2_LOCK")
      (libsource (lib "eagle-import") (part "CONNECTOR-M023.5MM-LOCK"))
    )
  )
  (nets
    (net (code "1") (name "+3V3") (class "Default")
      (node (ref "C11") (pin "1") (pinfunction "1_1") (pintype "passive"))
      (node (ref "C4") (pin "1") (pinfunction "1_1") (pintype "passive"))
      (node (ref "IC1") (pin "1") (pinfunction "SER_1") (pintype "input"))
      (node (ref "IC1") (pin "16") (pinfunction "VCC_16") (pintype "power_in"))
      (node (ref "IC1") (pin "9") (pinfunction "CLR_9") (pintype "input"))
      (node (ref "IC4") (pin "16") (pinfunction "VCC_16") (pintype "power_in"))
      (node (ref "IC4") (pin "9") (pinfunction "CLR_9") (pintype "input"))
      (node (ref "R1") (pin "2") (pinfunction "2_2") (pintype "passive"))
      (node (ref "R45") (pin "1") (pinfunction "1_1") (pintype "passive"))
      (node (ref "R46") (pin "2") (pinfunction "2_2") (pintype "passive"))
      (node (ref "R47") (pin "2") (pinfunction "2_2") (pintype "passive"))
      (node (ref "R48") (pin "2") (pinfunction "2_2") (pintype "passive"))
      (node (ref "R49") (pin "2") (pinfunction "2_2") (pintype "passive"))
      (node (ref "R50") (pin "2") (pinfunction "2_2") (pintype "passive"))
      (node (ref "R51") (pin "2") (pinfunction "2_2") (pintype "passive"))
      (node (ref "R52") (pin "2") (pinfunction "2_2") (pintype "passive"))
      (node (ref "R53") (pin "1") (pinfunction "1_1") (pintype "passive"))
      (node (ref "R54") (pin "1") (pinfunction "1_1") (pintype "passive"))
      (node (ref "R55") (pin "1") (pinfunction "1_1") (pintype "passive"))
      (node (ref "R56") (pin "1") (pinfunction "1_1") (pintype "passive"))
      (node (ref "R57") (pin "1") (pinfunction "1_1") (pintype "passive"))
      (node (ref "R58") (pin "1") (pinfunction "1_1") (pintype "passive"))
      (node (ref "R59") (pin "1") (pinfunction "1_1") (pintype "passive"))
      (node (ref "R60") (pin "1") (pinfunction "1_1") (pintype "passive"))
      (node (ref "RN2") (pin "1") (pinfunction "1_1") (pintype "passive"))
      (node (ref "RN5") (pin "1") (pinfunction "1_1") (pintype "passive"))
      (node (ref "SJ18") (pin "P$1") (pinfunction "1_P$1") (pintype "passive"))
      (node (ref "U$1") (pin "3V3") (pinfunction "3V3_3V3") (pintype "power_in"))
    )
    (net (code "2") (name "+5V") (class "Default")
      (node (ref "C3") (pin "1") (pinfunction "1_1") (pintype "passive"))
      (node (ref "C5") (pin "1") (pinfunction "1_1") (pintype "passive"))
      (node (ref "C8") (pin "1") (pinfunction "1_1") (pintype "passive"))
      (node (ref "C9") (pin "1") (pinfunction "1_1") (pintype "passive"))
      (node (ref "IC3") (pin "10") (pinfunction "SCL_10") (pintype "input"))
      (node (ref "IC3") (pin "16") (pinfunction "VCC_16") (pintype "power_in"))
      (node (ref "IC5") (pin "10") (pinfunction "SCL_10") (pintype "input"))
      (node (ref "IC5") (pin "16") (pinfunction "VCC_16") (pintype "power_in"))
      (node (ref "IC7") (pin "3") (pinfunction "VCC_3") (pintype "power_in"))
      (node (ref "JP10") (pin "2") (pinfunction "2_2") (pintype "passive"))
      (node (ref "JP11") (pin "3") (pinfunction "3_3") (pintype "passive"))
      (node (ref "JP11") (pin "4") (pinfunction "4_4") (pintype "passive"))
      (node (ref "JP12") (pin "3") (pinfunction "3_3") (pintype "passive"))
      (node (ref "JP12") (pin "4") (pinfunction "4_4") (pintype "passive"))
      (node (ref "JP13") (pin "6") (pinfunction "6_6") (pintype "passive"))
      (node (ref "JP14") (pin "6") (pinfunction "6_6") (pintype "passive"))
      (node (ref "JP15") (pin "6") (pinfunction "6_6") (pintype "passive"))
      (node (ref "JP16") (pin "3") (pinfunction "3_3") (pintype "passive"))
      (node (ref "JP16") (pin "4") (pinfunction "4_4") (pintype "passive"))
      (node (ref "JP7") (pin "3") (pinfunction "3_3") (pintype "passive"))
      (node (ref "JP7") (pin "4") (pinfunction "4_4") (pintype "passive"))
      (node (ref "JP8") (pin "3") (pinfunction "3_3") (pintype "passive"))
      (node (ref "R19") (pin "2") (pinfunction "2_2") (pintype "passive"))
      (node (ref "R20") (pin "2") (pinfunction "2_2") (pintype "passive"))
      (node (ref "R21") (pin "2") (pinfunction "2_2") (pintype "passive"))
      (node (ref "R22") (pin "1") (pinfunction "1_1") (pintype "passive"))
      (node (ref "R23") (pin "1") (pinfunction "1_1") (pintype "passive"))
      (node (ref "R24") (pin "1") (pinfunction "1_1") (pintype "passive"))
      (node (ref "R25") (pin "1") (pinfunction "1_1") (pintype "passive"))
      (node (ref "R26") (pin "1") (pinfunction "1_1") (pintype "passive"))
      (node (ref "R27") (pin "1") (pinfunction "1_1") (pintype "passive"))
      (node (ref "R62") (pin "1") (pinfunction "1_1") (pintype "passive"))
      (node (ref "R63") (pin "1") (pinfunction "1_1") (pintype "passive"))
      (node (ref "R64") (pin "1") (pinfunction "1_1") (pintype "passive"))
      (node (ref "R65") (pin "1") (pinfunction "1_1") (pintype "passive"))
      (node (ref "R66") (pin "1") (pinfunction "1_1") (pintype "passive"))
      (node (ref "R67") (pin "1") (pinfunction "1_1") (pintype "passive"))
      (node (ref "SJ1") (pin "P$2") (pinfunction "2_P$2") (pintype "passive"))
      (node (ref "SJ10") (pin "P$2") (pinfunction "2_P$2") (pintype "passive"))
      (node (ref "SJ4") (pin "P$2") (pinfunction "2_P$2") (pintype "passive"))
      (node (ref "SJ7") (pin "P$2") (pinfunction "2_P$2") (pintype "passive"))
      (node (ref "U$1") (pin "5V2") (pinfunction "5V2_5V2") (pintype "power_in"))
      (node (ref "U$6") (pin "3") (pinfunction "VDD_3") (pintype "power_in"))
      (node (ref "X1") (pin "1") (pinfunction "1_1") (pintype "passive"))
    )
    (net (code "3") (name "+12V") (class "Default")
      (node (ref "AP1509") (pin "1") (pinfunction "VIN_1") (pintype "bidirectional"))
      (node (ref "C10") (pin "1") (pinfunction "1_1") (pintype "passive"))
      (node (ref "C6") (pin "1") (pinfunction "1_1") (pintype "passive"))
      (node (ref "C7") (pin "1") (pinfunction "1_1") (pintype "passive"))
      (node (ref "IC10") (pin "5") (pinfunction "IN_5") (pintype "input"))
      (node (ref "IC6") (pin "4") (pinfunction "V+_4") (pintype "power_in"))
      (node (ref "IC9") (pin "4") (pinfunction "V+_4") (pintype "power_in"))
      (node (ref "J3") (pin "3") (pinfunction "3_3") (pintype "passive"))
      (node (ref "JP10") (pin "3") (pinfunction "3_3") (pintype "passive"))
      (node (ref "JP4") (pin "2") (pinfunction "2_2") (pintype "passive"))
      (node (ref "SJ11") (pin "P$2") (pinfunction "2_P$2") (pintype "passive"))
      (node (ref "SJ14") (pin "P$2") (pinfunction "2_P$2") (pintype "passive"))
      (node (ref "SJ2") (pin "P$2") (pinfunction "2_P$2") (pintype "passive"))
      (node (ref "SJ5") (pin "P$2") (pinfunction "2_P$2") (pintype "passive"))
      (node (ref "SJ8") (pin "P$2") (pinfunction "2_P$2") (pintype "passive"))
      (node (ref "U$2") (pin "6") (pinfunction "VDD_6") (pintype "power_in"))
      (node (ref "U$3") (pin "6") (pinfunction "VDD_6") (pintype "power_in"))
      (node (ref "U$4") (pin "6") (pinfunction "VDD_6") (pintype "power_in"))
      (node (ref "U$5") (pin "6") (pinfunction "VDD_6") (pintype "power_in"))
    )
    (net (code "4") (name "/AGND") (class "Default")
      (node (ref "U$1") (pin "AGND") (pinfunction "AGND_AGND") (pintype "power_in"))
    )
    (net (code "5") (name "/AVDD") (class "Default")
      (node (ref "U$1") (pin "AVDD") (pinfunction "AVDD_AVDD") (pintype "power_in"))
    )
    (net (code "6") (name "/CANH") (class "Default")
      (node (ref "IC7") (pin "7") (pinfunction "CANH_7") (pintype "bidirectional"))
      (node (ref "J1") (pin "1") (pinfunction "1_1") (pintype "passive"))
      (node (ref "J2") (pin "1") (pinfunction "1_1") (pintype "passive"))
      (node (ref "U$6") (pin "7") (pinfunction "CANH_7") (pintype "bidirectional"))
    )
    (net (code "7") (name "/CANL") (class "Default")
      (node (ref "IC7") (pin "6") (pinfunction "CANL_6") (pintype "bidirectional"))
      (node (ref "J1") (pin "2") (pinfunction "2_2") (pintype "passive"))
      (node (ref "J2") (pin "2") (pinfunction "2_2") (pintype "passive"))
      (node (ref "U$6") (pin "6") (pinfunction "CANL_6") (pintype "bidirectional"))
    )
    (net (code "8") (name "/GND4") (class "Default")
      (node (ref "U$1") (pin "GND4") (pinfunction "GND4_GND4") (pintype "power_in"))
    )
    (net (code "9") (name "/U5V") (class "Default")
      (node (ref "U$1") (pin "U5V") (pinfunction "U5V_U5V") (pintype "power_in"))
    )
    (net (code "10") (name "/VBAT") (class "Default")
      (node (ref "U$1") (pin "VBAT") (pinfunction "VBAT_VBAT") (pintype "power_in"))
    )
    (net (code "11") (name "/VDD") (class "Default")
      (node (ref "U$1") (pin "VDD") (pinfunction "VDD_VDD") (pintype "power_in"))
    )
    (net (code "12") (name "CANRX") (class "Default")
      (node (ref "IC7") (pin "4") (pinfunction "RXD_4") (pintype "output"))
      (node (ref "U$1") (pin "PB8") (pinfunction "PB8_PB8") (pintype "bidirectional"))
      (node (ref "U$6") (pin "4") (pinfunction "RXD_4") (pintype "bidirectional"))
    )
    (net (code "13") (name "CANTX") (class "Default")
      (node (ref "IC7") (pin "1") (pinfunction "TXD_1") (pintype "input"))
      (node (ref "U$1") (pin "PB9") (pinfunction "PB9_PB9") (pintype "bidirectional"))
      (node (ref "U$6") (pin "1") (pinfunction "TXD_1") (pintype "bidirectional"))
    )
    (net (code "14") (name "E_CS") (class "Default")
      (node (ref "JP9") (pin "4") (pinfunction "4_4") (pintype "passive"))
      (node (ref "R23") (pin "2") (pinfunction "2_2") (pintype "passive"))
      (node (ref "U$1") (pin "PC10") (pinfunction "PC10_PC10") (pintype "bidirectional"))
    )
    (net (code "15") (name "E_LAT") (class "Default")
      (node (ref "JP10") (pin "1") (pinfunction "1_1") (pintype "passive"))
      (node (ref "R22") (pin "2") (pinfunction "2_2") (pintype "passive"))
      (node (ref "U$1") (pin "PC11") (pinfunction "PC11_PC11") (pintype "bidirectional"))
    )
    (net (code "16") (name "GND") (class "Default")
      (node (ref "AP1509") (pin "4") (pinfunction "SD_4") (pintype "bidirectional"))
      (node (ref "AP1509") (pin "5") (pinfunction "GND1_5") (pintype "power_in"))
      (node (ref "AP1509") (pin "6") (pinfunction "GND2_6") (pintype "power_in"))
      (node (ref "AP1509") (pin "7") (pinfunction "GND3_7") (pintype "power_in"))
      (node (ref "AP1509") (pin "8") (pinfunction "GND4_8") (pintype "power_in"))
      (node (ref "C1") (pin "2") (pinfunction "2_2") (pintype "passive"))
      (node (ref "C10") (pin "2") (pinfunction "2_2") (pintype "passive"))
      (node (ref "C11") (pin "2") (pinfunction "2_2") (pintype "passive"))
      (node (ref "C2") (pin "-") (pinfunction "-_-") (pintype "passive"))
      (node (ref "C3") (pin "2") (pinfunction "2_2") (pintype "passive"))
      (node (ref "C4") (pin "2") (pinfunction "2_2") (pintype "passive"))
      (node (ref "C5") (pin "2") (pinfunction "2_2") (pintype "passive"))
      (node (ref "C6") (pin "2") (pinfunction "2_2") (pintype "passive"))
      (node (ref "C7") (pin "2") (pinfunction "2_2") (pintype "passive"))
      (node (ref "C8") (pin "2") (pinfunction "2_2") (pintype "passive"))
      (node (ref "C9") (pin "2") (pinfunction "2_2") (pintype "passive"))
      (node (ref "D1") (pin "A") (pinfunction "A_A") (pintype "passive"))
      (node (ref "IC1") (pin "6") (pinfunction "INH_6") (pintype "input"))
      (node (ref "IC1") (pin "8") (pinfunction "GND_8") (pintype "power_in"))
      (node (ref "IC10") (pin "2") (pinfunction "GNDSIG_2") (pintype "input"))
      (node (ref "IC10") (pin "3") (pinfunction "~{ON/OFF}_3") (pintype "input"))
      (node (ref "IC10") (pin "4") (pinfunction "GND_4") (pintype "power_in"))
      (node (ref "IC3") (pin "13") (pinfunction "G_13") (pintype "input"))
      (node (ref "IC3") (pin "8") (pinfunction "GND_8") (pintype "power_in"))
      (node (ref "IC4") (pin "6") (pinfunction "INH_6") (pintype "input"))
      (node (ref "IC4") (pin "8") (pinfunction "GND_8") (pintype "power_in"))
      (node (ref "IC5") (pin "13") (pinfunction "G_13") (pintype "input"))
      (node (ref "IC5") (pin "8") (pinfunction "GND_8") (pintype "power_in"))
      (node (ref "IC6") (pin "11") (pinfunction "V-_11") (pintype "power_in"))
      (node (ref "IC7") (pin "2") (pinfunction "GND_2") (pintype "power_in"))
      (node (ref "IC9") (pin "11") (pinfunction "V-_11") (pintype "power_in"))
      (node (ref "J1") (pin "3") (pinfunction "3_3") (pintype "passive"))
      (node (ref "J1") (pin "6") (pinfunction "6_6") (pintype "passive"))
      (node (ref "J1") (pin "7") (pinfunction "7_7") (pintype "passive"))
      (node (ref "J2") (pin "3") (pinfunction "3_3") (pintype "passive"))
      (node (ref "J2") (pin "6") (pinfunction "6_6") (pintype "passive"))
      (node (ref "J2") (pin "7") (pinfunction "7_7") (pintype "passive"))
      (node (ref "J3") (pin "1") (pinfunction "1_1") (pintype "passive"))
      (node (ref "JP10") (pin "4") (pinfunction "4_4") (pintype "passive"))
      (node (ref "JP11") (pin "5") (pinfunction "5_5") (pintype "passive"))
      (node (ref "JP11") (pin "6") (pinfunction "6_6") (pintype "passive"))
      (node (ref "JP12") (pin "5") (pinfunction "5_5") (pintype "passive"))
      (node (ref "JP12") (pin "6") (pinfunction "6_6") (pintype "passive"))
      (node (ref "JP13") (pin "5") (pinfunction "5_5") (pintype "passive"))
      (node (ref "JP14") (pin "5") (pinfunction "5_5") (pintype "passive"))
      (node (ref "JP15") (pin "5") (pinfunction "5_5") (pintype "passive"))
      (node (ref "JP16") (pin "5") (pinfunction "5_5") (pintype "passive"))
      (node (ref "JP16") (pin "6") (pinfunction "6_6") (pintype "passive"))
      (node (ref "JP7") (pin "5") (pinfunction "5_5") (pintype "passive"))
      (node (ref "JP7") (pin "6") (pinfunction "6_6") (pintype "passive"))
      (node (ref "JP8") (pin "4") (pinfunction "4_4") (pintype "passive"))
      (node (ref "Q1") (pin "2") (pinfunction "S_2") (pintype "passive"))
      (node (ref "Q10") (pin "2") (pinfunction "S_2") (pintype "passive"))
      (node (ref "Q11") (pin "2") (pinfunction "S_2") (pintype "passive"))
      (node (ref "Q12") (pin "2") (pinfunction "S_2") (pintype "passive"))
      (node (ref "Q13") (pin "2") (pinfunction "S_2") (pintype "passive"))
      (node (ref "Q14") (pin "2") (pinfunction "S_2") (pintype "passive"))
      (node (ref "Q15") (pin "2") (pinfunction "S_2") (pintype "passive"))
      (node (ref "Q16") (pin "2") (pinfunction "S_2") (pintype "passive"))
      (node (ref "Q2") (pin "2") (pinfunction "S_2") (pintype "passive"))
      (node (ref "Q3") (pin "2") (pinfunction "S_2") (pintype "passive"))
      (node (ref "Q4") (pin "2") (pinfunction "S_2") (pintype "passive"))
      (node (ref "Q5") (pin "2") (pinfunction "S_2") (pintype "passive"))
      (node (ref "Q6") (pin "2") (pinfunction "S_2") (pintype "passive"))
      (node (ref "Q7") (pin "2") (pinfunction "S_2") (pintype "passive"))
      (node (ref "Q8") (pin "2") (pinfunction "S_2") (pintype "passive"))
      (node (ref "Q9") (pin "2") (pinfunction "S_2") (pintype "passive"))
      (node (ref "R2") (pin "1") (pinfunction "1_1") (pintype "passive"))
      (node (ref "R61") (pin "2") (pinfunction "2_2") (pintype "passive"))
      (node (ref "SJ12") (pin "P$2") (pinfunction "2_P$2") (pintype "passive"))
      (node (ref "SJ3") (pin "2") (pinfunction "2_2") (pintype "passive"))
      (node (ref "SJ6") (pin "P$2") (pinfunction "2_P$2") (pintype "passive"))
      (node (ref "SJ9") (pin "2") (pinfunction "2_2") (pintype "passive"))
      (node (ref "U$1") (pin "GND3") (pinfunction "GND3_GND3") (pintype "power_in"))
      (node (ref "U$1") (pin "GND5") (pinfunction "GND5_GND5") (pintype "power_in"))
      (node (ref "U$1") (pin "GND6") (pinfunction "GND6_GND6") (pintype "power_in"))
      (node (ref "U$1") (pin "GND7") (pinfunction "GND7_GND7") (pintype "power_in"))
      (node (ref "U$1") (pin "GND8") (pinfunction "GND8_GND8") (pintype "power_in"))
      (node (ref "U$2") (pin "3") (pinfunction "VSS_3") (pintype "power_in"))
      (node (ref "U$3") (pin "3") (pinfunction "VSS_3") (pintype "power_in"))
      (node (ref "U$4") (pin "3") (pinfunction "VSS_3") (pintype "power_in"))
      (node (ref "U$5") (pin "3") (pinfunction "VSS_3") (pintype "power_in"))
      (node (ref "U$6") (pin "2") (pinfunction "VSS_2") (pintype "power_in"))
      (node (ref "X1") (pin "2") (pinfunction "2_2") (pintype "passive"))
    )
    (net (code "17") (name "I2CSCL") (class "Default")
      (node (ref "JP8") (pin "2") (pinfunction "2_2") (pintype "passive"))
      (node (ref "R63") (pin "2") (pinfunction "2_2") (pintype "passive"))
      (node (ref "U$1") (pin "PB6") (pinfunction "PB6_PB6") (pintype "bidirectional"))
    )
    (net (code "18") (name "I2CSDA") (class "Default")
      (node (ref "JP8") (pin "1") (pinfunction "1_1") (pintype "passive"))
      (node (ref "R62") (pin "2") (pinfunction "2_2") (pintype "passive"))
      (node (ref "U$1") (pin "PB7") (pinfunction "PB7_PB7") (pintype "bidirectional"))
    )
    (net (code "19") (name "ILAT") (class "Default")
      (node (ref "IC1") (pin "15") (pinfunction "SH/~{LD}_15") (pintype "input"))
      (node (ref "IC4") (pin "15") (pinfunction "SH/~{LD}_15") (pintype "input"))
      (node (ref "U$1") (pin "PA6") (pinfunction "PA6_PA6") (pintype "bidirectional"))
    )
    (net (code "20") (name "MISO") (class "Default")
      (node (ref "JP9") (pin "1") (pinfunction "1_1") (pintype "passive"))
      (node (ref "U$1") (pin "PB4") (pinfunction "PB4_PB4") (pintype "bidirectional"))
    )
    (net (code "21") (name "MISO2") (class "Default")
      (node (ref "IC4") (pin "13") (pinfunction "QH_13") (pintype "output"))
      (node (ref "SJ13") (pin "P$2") (pinfunction "2_P$2") (pintype "passive"))
      (node (ref "U$1") (pin "PC2") (pinfunction "PC2_PC2") (pintype "bidirectional"))
    )
    (net (code "22") (name "MOSI") (class "Default")
      (node (ref "IC5") (pin "14") (pinfunction "SER_14") (pintype "input"))
      (node (ref "R20") (pin "1") (pinfunction "1_1") (pintype "passive"))
      (node (ref "SJ15") (pin "1") (pinfunction "1_1") (pintype "passive"))
      (node (ref "SJ17") (pin "P$2") (pinfunction "2_P$2") (pintype "passive"))
      (node (ref "U$1") (pin "PB5") (pinfunction "PB5_PB5") (pintype "bidirectional"))
    )
    (net (code "23") (name "Net-(AP1509-VOUT)") (class "Default")
      (node (ref "AP1509") (pin "2") (pinfunction "VOUT_2") (pintype "bidirectional"))
      (node (ref "D1") (pin "C") (pinfunction "C_C") (pintype "passive"))
      (node (ref "IC10") (pin "7") (pinfunction "OUT_7") (pintype "passive"))
      (node (ref "L1") (pin "2") (pinfunction "2_2") (pintype "passive"))
    )
    (net (code "24") (name "Net-(D2-PadA)") (class "Default")
      (node (ref "D2") (pin "A") (pinfunction "A_A") (pintype "passive"))
      (node (ref "JP4") (pin "4") (pinfunction "4_4") (pintype "passive"))
    )
    (net (code "25") (name "Net-(D2-PadC)") (class "Default")
      (node (ref "D2") (pin "C") (pinfunction "C_C") (pintype "passive"))
      (node (ref "JP4") (pin "1") (pinfunction "1_1") (pintype "passive"))
    )
    (net (code "26") (name "Net-(IC1A-A)") (class "Default")
      (node (ref "IC1") (pin "2") (pinfunction "A_2") (pintype "input"))
      (node (ref "R36") (pin "1") (pinfunction "1_1") (pintype "passive"))
      (node (ref "RN4") (pin "9") (pinfunction "2_9") (pintype "passive"))
    )
    (net (code "27") (name "Net-(IC1A-B)") (class "Default")
      (node (ref "IC1") (pin "3") (pinfunction "B_3") (pintype "input"))
      (node (ref "R37") (pin "1") (pinfunction "1_1") (pintype "passive"))
      (node (ref "RN4") (pin "10") (pinfunction "2_10") (pintype "passive"))
    )
    (net (code "28") (name "Net-(IC1A-C)") (class "Default")
      (node (ref "IC1") (pin "4") (pinfunction "C_4") (pintype "input"))
      (node (ref "R38") (pin "1") (pinfunction "1_1") (pintype "passive"))
      (node (ref "RN4") (pin "11") (pinfunction "2_11") (pintype "passive"))
    )
    (net (code "29") (name "Net-(IC1A-D)") (class "Default")
      (node (ref "IC1") (pin "5") (pinfunction "D_5") (pintype "input"))
      (node (ref "R39") (pin "1") (pinfunction "1_1") (pintype "passive"))
      (node (ref "RN4") (pin "12") (pinfunction "2_12") (pintype "passive"))
    )
    (net (code "30") (name "Net-(IC1A-E)") (class "Default")
      (node (ref "IC1") (pin "10") (pinfunction "E_10") (pintype "input"))
      (node (ref "R41") (pin "1") (pinfunction "1_1") (pintype "passive"))
      (node (ref "RN4") (pin "13") (pinfunction "2_13") (pintype "passive"))
    )
    (net (code "31") (name "Net-(IC1A-F)") (class "Default")
      (node (ref "IC1") (pin "11") (pinfunction "F_11") (pintype "input"))
      (node (ref "R42") (pin "1") (pinfunction "1_1") (pintype "passive"))
      (node (ref "RN4") (pin "14") (pinfunction "2_14") (pintype "passive"))
    )
    (net (code "32") (name "Net-(IC1A-G)") (class "Default")
      (node (ref "IC1") (pin "12") (pinfunction "G_12") (pintype "input"))
      (node (ref "R43") (pin "1") (pinfunction "1_1") (pintype "passive"))
      (node (ref "RN4") (pin "15") (pinfunction "2_15") (pintype "passive"))
    )
    (net (code "33") (name "Net-(IC1A-H)") (class "Default")
      (node (ref "IC1") (pin "14") (pinfunction "H_14") (pintype "input"))
      (node (ref "R44") (pin "1") (pinfunction "1_1") (pintype "passive"))
      (node (ref "RN4") (pin "16") (pinfunction "2_16") (pintype "passive"))
    )
    (net (code "34") (name "Net-(IC2-CD+)") (class "Default")
      (node (ref "IC2") (pin "10") (pinfunction "CD+_10") (pintype "passive"))
      (node (ref "SJ4") (pin "P$1") (pinfunction "1_P$1") (pintype "passive"))
      (node (ref "SJ5") (pin "P$1") (pinfunction "1_P$1") (pintype "passive"))
      (node (ref "SJ6") (pin "P$1") (pinfunction "1_P$1") (pintype "passive"))
    )
    (net (code "35") (name "Net-(IC2-GND)") (class "Default")
      (node (ref "IC2") (pin "9") (pinfunction "GND_9") (pintype "power_in"))
      (node (ref "SJ1") (pin "P$1") (pinfunction "1_P$1") (pintype "passive"))
      (node (ref "SJ2") (pin "P$1") (pinfunction "1_P$1") (pintype "passive"))
      (node (ref "SJ3") (pin "1") (pinfunction "1_1") (pintype "passive"))
    )
    (net (code "36") (name "Net-(IC2-I1)") (class "Default")
      (node (ref "IC2") (pin "1") (pinfunction "I1_1") (pintype "input"))
      (node (ref "IC5") (pin "15") (pinfunction "QA_15") (pintype "tri_state"))
      (node (ref "R3") (pin "1") (pinfunction "1_1") (pintype "passive"))
    )
    (net (code "37") (name "Net-(IC2-I2)") (class "Default")
      (node (ref "IC2") (pin "2") (pinfunction "I2_2") (pintype "input"))
      (node (ref "IC5") (pin "1") (pinfunction "QB_1") (pintype "tri_state"))
      (node (ref "R4") (pin "1") (pinfunction "1_1") (pintype "passive"))
    )
    (net (code "38") (name "Net-(IC2-I3)") (class "Default")
      (node (ref "IC2") (pin "3") (pinfunction "I3_3") (pintype "input"))
      (node (ref "IC5") (pin "2") (pinfunction "QC_2") (pintype "tri_state"))
      (node (ref "R5") (pin "1") (pinfunction "1_1") (pintype "passive"))
    )
    (net (code "39") (name "Net-(IC2-I4)") (class "Default")
      (node (ref "IC2") (pin "4") (pinfunction "I4_4") (pintype "input"))
      (node (ref "IC5") (pin "3") (pinfunction "QD_3") (pintype "tri_state"))
      (node (ref "R6") (pin "1") (pinfunction "1_1") (pintype "passive"))
    )
    (net (code "40") (name "Net-(IC2-I5)") (class "Default")
      (node (ref "IC2") (pin "5") (pinfunction "I5_5") (pintype "input"))
      (node (ref "IC5") (pin "4") (pinfunction "QE_4") (pintype "tri_state"))
      (node (ref "R7") (pin "1") (pinfunction "1_1") (pintype "passive"))
    )
    (net (code "41") (name "Net-(IC2-I6)") (class "Default")
      (node (ref "IC2") (pin "6") (pinfunction "I6_6") (pintype "input"))
      (node (ref "IC5") (pin "5") (pinfunction "QF_5") (pintype "tri_state"))
      (node (ref "R8") (pin "1") (pinfunction "1_1") (pintype "passive"))
    )
    (net (code "42") (name "Net-(IC2-I7)") (class "Default")
      (node (ref "IC2") (pin "7") (pinfunction "I7_7") (pintype "input"))
      (node (ref "IC5") (pin "6") (pinfunction "QG_6") (pintype "tri_state"))
      (node (ref "R9") (pin "1") (pinfunction "1_1") (pintype "passive"))
    )
    (net (code "43") (name "Net-(IC2-I8)") (class "Default")
      (node (ref "IC2") (pin "8") (pinfunction "I8_8") (pintype "input"))
      (node (ref "IC5") (pin "7") (pinfunction "QH_7") (pintype "tri_state"))
      (node (ref "R10") (pin "1") (pinfunction "1_1") (pintype "passive"))
    )
    (net (code "44") (name "Net-(IC2-O1)") (class "Default")
      (node (ref "IC2") (pin "18") (pinfunction "O1_18") (pintype "open_collector"))
      (node (ref "JP1") (pin "1") (pinfunction "1_1") (pintype "passive"))
      (node (ref "Q1") (pin "3") (pinfunction "D_3") (pintype "passive"))
    )
    (net (code "45") (name "Net-(IC2-O2)") (class "Default")
      (node (ref "IC2") (pin "17") (pinfunction "O2_17") (pintype "open_collector"))
      (node (ref "JP1") (pin "2") (pinfunction "2_2") (pintype "passive"))
      (node (ref "Q2") (pin "3") (pinfunction "D_3") (pintype "passive"))
    )
    (net (code "46") (name "Net-(IC2-O3)") (class "Default")
      (node (ref "IC2") (pin "16") (pinfunction "O3_16") (pintype "open_collector"))
      (node (ref "JP1") (pin "3") (pinfunction "3_3") (pintype "passive"))
      (node (ref "Q3") (pin "3") (pinfunction "D_3") (pintype "passive"))
    )
    (net (code "47") (name "Net-(IC2-O4)") (class "Default")
      (node (ref "IC2") (pin "15") (pinfunction "O4_15") (pintype "open_collector"))
      (node (ref "JP1") (pin "4") (pinfunction "4_4") (pintype "passive"))
      (node (ref "Q4") (pin "3") (pinfunction "D_3") (pintype "passive"))
    )
    (net (code "48") (name "Net-(IC2-O5)") (class "Default")
      (node (ref "IC2") (pin "14") (pinfunction "O5_14") (pintype "open_collector"))
      (node (ref "JP1") (pin "5") (pinfunction "5_5") (pintype "passive"))
      (node (ref "Q5") (pin "3") (pinfunction "D_3") (pintype "passive"))
    )
    (net (code "49") (name "Net-(IC2-O6)") (class "Default")
      (node (ref "IC2") (pin "13") (pinfunction "O6_13") (pintype "open_collector"))
      (node (ref "JP1") (pin "6") (pinfunction "6_6") (pintype "passive"))
      (node (ref "Q6") (pin "3") (pinfunction "D_3") (pintype "passive"))
    )
    (net (code "50") (name "Net-(IC2-O7)") (class "Default")
      (node (ref "IC2") (pin "12") (pinfunction "O7_12") (pintype "open_collector"))
      (node (ref "JP1") (pin "7") (pinfunction "7_7") (pintype "passive"))
      (node (ref "Q7") (pin "3") (pinfunction "D_3") (pintype "passive"))
    )
    (net (code "51") (name "Net-(IC2-O8)") (class "Default")
      (node (ref "IC2") (pin "11") (pinfunction "O8_11") (pintype "open_collector"))
      (node (ref "JP1") (pin "8") (pinfunction "8_8") (pintype "passive"))
      (node (ref "Q8") (pin "3") (pinfunction "D_3") (pintype "passive"))
    )
    (net (code "52") (name "Net-(IC3A-QA)") (class "Default")
      (node (ref "IC3") (pin "15") (pinfunction "QA_15") (pintype "tri_state"))
      (node (ref "IC8") (pin "1") (pinfunction "I1_1") (pintype "input"))
      (node (ref "R11") (pin "1") (pinfunction "1_1") (pintype "passive"))
    )
    (net (code "53") (name "Net-(IC3A-QB)") (class "Default")
      (node (ref "IC3") (pin "1") (pinfunction "QB_1") (pintype "tri_state"))
      (node (ref "IC8") (pin "2") (pinfunction "I2_2") (pintype "input"))
      (node (ref "R12") (pin "1") (pinfunction "1_1") (pintype "passive"))
    )
    (net (code "54") (name "Net-(IC3A-QC)") (class "Default")
      (node (ref "IC3") (pin "2") (pinfunction "QC_2") (pintype "tri_state"))
      (node (ref "IC8") (pin "3") (pinfunction "I3_3") (pintype "input"))
      (node (ref "R13") (pin "1") (pinfunction "1_1") (pintype "passive"))
    )
    (net (code "55") (name "Net-(IC3A-QD)") (class "Default")
      (node (ref "IC3") (pin "3") (pinfunction "QD_3") (pintype "tri_state"))
      (node (ref "IC8") (pin "4") (pinfunction "I4_4") (pintype "input"))
      (node (ref "R14") (pin "1") (pinfunction "1_1") (pintype "passive"))
    )
    (net (code "56") (name "Net-(IC3A-QE)") (class "Default")
      (node (ref "IC3") (pin "4") (pinfunction "QE_4") (pintype "tri_state"))
      (node (ref "IC8") (pin "5") (pinfunction "I5_5") (pintype "input"))
      (node (ref "R15") (pin "1") (pinfunction "1_1") (pintype "passive"))
    )
    (net (code "57") (name "Net-(IC3A-QF)") (class "Default")
      (node (ref "IC3") (pin "5") (pinfunction "QF_5") (pintype "tri_state"))
      (node (ref "IC8") (pin "6") (pinfunction "I6_6") (pintype "input"))
      (node (ref "R16") (pin "1") (pinfunction "1_1") (pintype "passive"))
    )
    (net (code "58") (name "Net-(IC3A-QG)") (class "Default")
      (node (ref "IC3") (pin "6") (pinfunction "QG_6") (pintype "tri_state"))
      (node (ref "IC8") (pin "7") (pinfunction "I7_7") (pintype "input"))
      (node (ref "R17") (pin "1") (pinfunction "1_1") (pintype "passive"))
    )
    (net (code "59") (name "Net-(IC3A-QH)") (class "Default")
      (node (ref "IC3") (pin "7") (pinfunction "QH_7") (pintype "tri_state"))
      (node (ref "IC8") (pin "8") (pinfunction "I8_8") (pintype "input"))
      (node (ref "R18") (pin "1") (pinfunction "1_1") (pintype "passive"))
    )
    (net (code "60") (name "Net-(IC4A-A)") (class "Default")
      (node (ref "IC4") (pin "2") (pinfunction "A_2") (pintype "input"))
      (node (ref "R28") (pin "1") (pinfunction "1_1") (pintype "passive"))
      (node (ref "RN1") (pin "9") (pinfunction "2_9") (pintype "passive"))
    )
    (net (code "61") (name "Net-(IC4A-B)") (class "Default")
      (node (ref "IC4") (pin "3") (pinfunction "B_3") (pintype "input"))
      (node (ref "R29") (pin "1") (pinfunction "1_1") (pintype "passive"))
      (node (ref "RN1") (pin "10") (pinfunction "2_10") (pintype "passive"))
    )
    (net (code "62") (name "Net-(IC4A-C)") (class "Default")
      (node (ref "IC4") (pin "4") (pinfunction "C_4") (pintype "input"))
      (node (ref "R30") (pin "1") (pinfunction "1_1") (pintype "passive"))
      (node (ref "RN1") (pin "11") (pinfunction "2_11") (pintype "passive"))
    )
    (net (code "63") (name "Net-(IC4A-D)") (class "Default")
      (node (ref "IC4") (pin "5") (pinfunction "D_5") (pintype "input"))
      (node (ref "R31") (pin "1") (pinfunction "1_1") (pintype "passive"))
      (node (ref "RN1") (pin "12") (pinfunction "2_12") (pintype "passive"))
    )
    (net (code "64") (name "Net-(IC4A-E)") (class "Default")
      (node (ref "IC4") (pin "10") (pinfunction "E_10") (pintype "input"))
      (node (ref "R32") (pin "1") (pinfunction "1_1") (pintype "passive"))
      (node (ref "RN1") (pin "13") (pinfunction "2_13") (pintype "passive"))
    )
    (net (code "65") (name "Net-(IC4A-F)") (class "Default")
      (node (ref "IC4") (pin "11") (pinfunction "F_11") (pintype "input"))
      (node (ref "R33") (pin "1") (pinfunction "1_1") (pintype "passive"))
      (node (ref "RN1") (pin "14") (pinfunction "2_14") (pintype "passive"))
    )
    (net (code "66") (name "Net-(IC4A-G)") (class "Default")
      (node (ref "IC4") (pin "12") (pinfunction "G_12") (pintype "input"))
      (node (ref "R34") (pin "1") (pinfunction "1_1") (pintype "passive"))
      (node (ref "RN1") (pin "15") (pinfunction "2_15") (pintype "passive"))
    )
    (net (code "67") (name "Net-(IC4A-H)") (class "Default")
      (node (ref "IC4") (pin "14") (pinfunction "H_14") (pintype "input"))
      (node (ref "R35") (pin "1") (pinfunction "1_1") (pintype "passive"))
      (node (ref "RN1") (pin "16") (pinfunction "2_16") (pintype "passive"))
    )
    (net (code "68") (name "Net-(IC6A--IN)") (class "Default")
      (node (ref "IC6") (pin "13") (pinfunction "-IN_13") (pintype "input"))
      (node (ref "IC6") (pin "2") (pinfunction "-IN_2") (pintype "input"))
      (node (ref "IC6") (pin "6") (pinfunction "-IN_6") (pintype "input"))
      (node (ref "IC6") (pin "9") (pinfunction "-IN_9") (pintype "input"))
      (node (ref "IC9") (pin "13") (pinfunction "-IN_13") (pintype "input"))
      (node (ref "IC9") (pin "2") (pinfunction "-IN_2") (pintype "input"))
      (node (ref "IC9") (pin "6") (pinfunction "-IN_6") (pintype "input"))
      (node (ref "IC9") (pin "9") (pinfunction "-IN_9") (pintype "input"))
      (node (ref "R1") (pin "1") (pinfunction "1_1") (pintype "passive"))
      (node (ref "R2") (pin "2") (pinfunction "2_2") (pintype "passive"))
    )
    (net (code "69") (name "Net-(IC6A-OUT)") (class "Default")
      (node (ref "IC6") (pin "1") (pinfunction "OUT_1") (pintype "output"))
      (node (ref "JP15") (pin "3") (pinfunction "3_3") (pintype "passive"))
      (node (ref "JP5") (pin "3") (pinfunction "3_3") (pintype "passive"))
      (node (ref "U$5") (pin "5") (pinfunction "O_5") (pintype "output"))
    )
    (net (code "70") (name "Net-(IC6B-OUT)") (class "Default")
      (node (ref "IC6") (pin "7") (pinfunction "OUT_7") (pintype "output"))
      (node (ref "JP15") (pin "1") (pinfunction "1_1") (pintype "passive"))
      (node (ref "JP5") (pin "1") (pinfunction "1_1") (pintype "passive"))
      (node (ref "U$4") (pin "7") (pinfunction "O_7") (pintype "output"))
    )
    (net (code "71") (name "Net-(IC6C-OUT)") (class "Default")
      (node (ref "IC6") (pin "8") (pinfunction "OUT_8") (pintype "output"))
      (node (ref "JP15") (pin "2") (pinfunction "2_2") (pintype "passive"))
      (node (ref "JP5") (pin "2") (pinfunction "2_2") (pintype "passive"))
      (node (ref "U$4") (pin "5") (pinfunction "O_5") (pintype "output"))
    )
    (net (code "72") (name "Net-(IC6D-OUT)") (class "Default")
      (node (ref "IC6") (pin "14") (pinfunction "OUT_14") (pintype "output"))
      (node (ref "JP15") (pin "4") (pinfunction "4_4") (pintype "passive"))
      (node (ref "JP5") (pin "4") (pinfunction "4_4") (pintype "passive"))
      (node (ref "U$5") (pin "7") (pinfunction "O_7") (pintype "output"))
    )
    (net (code "73") (name "Net-(IC7-RS)") (class "Default")
      (node (ref "IC7") (pin "8") (pinfunction "RS_8") (pintype "input"))
      (node (ref "R61") (pin "1") (pinfunction "1_1") (pintype "passive"))
      (node (ref "U$6") (pin "8") (pinfunction "RS_8") (pintype "bidirectional"))
    )
    (net (code "74") (name "Net-(IC7-VREF)") (class "Default")
      (node (ref "IC7") (pin "5") (pinfunction "VREF_5") (pintype "output"))
      (node (ref "SJ18") (pin "P$2") (pinfunction "2_P$2") (pintype "passive"))
      (node (ref "U$6") (pin "5") (pinfunction "VREF_5") (pintype "bidirectional"))
    )
    (net (code "75") (name "Net-(IC8-CD+)") (class "Default")
      (node (ref "IC8") (pin "10") (pinfunction "CD+_10") (pintype "passive"))
      (node (ref "SJ10") (pin "P$1") (pinfunction "1_P$1") (pintype "passive"))
      (node (ref "SJ11") (pin "P$1") (pinfunction "1_P$1") (pintype "passive"))
      (node (ref "SJ12") (pin "P$1") (pinfunction "1_P$1") (pintype "passive"))
    )
    (net (code "76") (name "Net-(IC8-GND)") (class "Default")
      (node (ref "IC8") (pin "9") (pinfunction "GND_9") (pintype "power_in"))
      (node (ref "SJ7") (pin "P$1") (pinfunction "1_P$1") (pintype "passive"))
      (node (ref "SJ8") (pin "P$1") (pinfunction "1_P$1") (pintype "passive"))
      (node (ref "SJ9") (pin "1") (pinfunction "1_1") (pintype "passive"))
    )
    (net (code "77") (name "Net-(IC8-O1)") (class "Default")
      (node (ref "IC8") (pin "18") (pinfunction "O1_18") (pintype "open_collector"))
      (node (ref "JP6") (pin "1") (pinfunction "1_1") (pintype "passive"))
      (node (ref "Q9") (pin "3") (pinfunction "D_3") (pintype "passive"))
    )
    (net (code "78") (name "Net-(IC8-O2)") (class "Default")
      (node (ref "IC8") (pin "17") (pinfunction "O2_17") (pintype "open_collector"))
      (node (ref "JP6") (pin "2") (pinfunction "2_2") (pintype "passive"))
      (node (ref "Q10") (pin "3") (pinfunction "D_3") (pintype "passive"))
    )
    (net (code "79") (name "Net-(IC8-O3)") (class "Default")
      (node (ref "IC8") (pin "16") (pinfunction "O3_16") (pintype "open_collector"))
      (node (ref "JP6") (pin "3") (pinfunction "3_3") (pintype "passive"))
      (node (ref "Q11") (pin "3") (pinfunction "D_3") (pintype "passive"))
    )
    (net (code "80") (name "Net-(IC8-O4)") (class "Default")
      (node (ref "IC8") (pin "15") (pinfunction "O4_15") (pintype "open_collector"))
      (node (ref "JP6") (pin "4") (pinfunction "4_4") (pintype "passive"))
      (node (ref "Q12") (pin "3") (pinfunction "D_3") (pintype "passive"))
    )
    (net (code "81") (name "Net-(IC8-O5)") (class "Default")
      (node (ref "IC8") (pin "14") (pinfunction "O5_14") (pintype "open_collector"))
      (node (ref "JP6") (pin "5") (pinfunction "5_5") (pintype "passive"))
      (node (ref "Q13") (pin "3") (pinfunction "D_3") (pintype "passive"))
    )
    (net (code "82") (name "Net-(IC8-O6)") (class "Default")
      (node (ref "IC8") (pin "13") (pinfunction "O6_13") (pintype "open_collector"))
      (node (ref "JP6") (pin "6") (pinfunction "6_6") (pintype "passive"))
      (node (ref "Q14") (pin "3") (pinfunction "D_3") (pintype "passive"))
    )
    (net (code "83") (name "Net-(IC8-O7)") (class "Default")
      (node (ref "IC8") (pin "12") (pinfunction "O7_12") (pintype "open_collector"))
      (node (ref "JP6") (pin "7") (pinfunction "7_7") (pintype "passive"))
      (node (ref "Q15") (pin "3") (pinfunction "D_3") (pintype "passive"))
    )
    (net (code "84") (name "Net-(IC8-O8)") (class "Default")
      (node (ref "IC8") (pin "11") (pinfunction "O8_11") (pintype "open_collector"))
      (node (ref "JP6") (pin "8") (pinfunction "8_8") (pintype "passive"))
      (node (ref "Q16") (pin "3") (pinfunction "D_3") (pintype "passive"))
    )
    (net (code "85") (name "Net-(IC9A-OUT)") (class "Default")
      (node (ref "IC9") (pin "1") (pinfunction "OUT_1") (pintype "output"))
      (node (ref "JP15") (pin "9") (pinfunction "9_9") (pintype "passive"))
      (node (ref "JP5") (pin "7") (pinfunction "7_7") (pintype "passive"))
      (node (ref "U$3") (pin "5") (pinfunction "O_5") (pintype "output"))
    )
    (net (code "86") (name "Net-(IC9B-OUT)") (class "Default")
      (node (ref "IC9") (pin "7") (pinfunction "OUT_7") (pintype "output"))
      (node (ref "JP15") (pin "7") (pinfunction "7_7") (pintype "passive"))
      (node (ref "JP5") (pin "5") (pinfunction "5_5") (pintype "passive"))
      (node (ref "U$2") (pin "7") (pinfunction "O_7") (pintype "output"))
    )
    (net (code "87") (name "Net-(IC9C-OUT)") (class "Default")
      (node (ref "IC9") (pin "8") (pinfunction "OUT_8") (pintype "output"))
      (node (ref "JP15") (pin "8") (pinfunction "8_8") (pintype "passive"))
      (node (ref "JP5") (pin "6") (pinfunction "6_6") (pintype "passive"))
      (node (ref "U$2") (pin "5") (pinfunction "O_5") (pintype "output"))
    )
    (net (code "88") (name "Net-(IC9D-OUT)") (class "Default")
      (node (ref "IC9") (pin "14") (pinfunction "OUT_14") (pintype "output"))
      (node (ref "JP15") (pin "10") (pinfunction "10_10") (pintype "passive"))
      (node (ref "JP5") (pin "8") (pinfunction "8_8") (pintype "passive"))
      (node (ref "U$3") (pin "7") (pinfunction "O_7") (pintype "output"))
    )
    (net (code "89") (name "Net-(J1-Pad4)") (class "Default")
      (node (ref "J1") (pin "4") (pinfunction "4_4") (pintype "passive"))
      (node (ref "J2") (pin "4") (pinfunction "4_4") (pintype "passive"))
    )
    (net (code "90") (name "Net-(J1-Pad5)") (class "Default")
      (node (ref "J1") (pin "5") (pinfunction "5_5") (pintype "passive"))
      (node (ref "J2") (pin "5") (pinfunction "5_5") (pintype "passive"))
    )
    (net (code "91") (name "Net-(J1-Pad8)") (class "Default")
      (node (ref "J1") (pin "8") (pinfunction "8_8") (pintype "passive"))
      (node (ref "J2") (pin "8") (pinfunction "8_8") (pintype "passive"))
      (node (ref "R40") (pin "1") (pinfunction "1_1") (pintype "passive"))
    )
    (net (code "92") (name "Net-(JP4-Pad3)") (class "Default")
      (node (ref "JP4") (pin "3") (pinfunction "3_3") (pintype "passive"))
      (node (ref "R40") (pin "2") (pinfunction "2_2") (pintype "passive"))
    )
    (net (code "93") (name "Net-(JP13-Pad1)") (class "Default")
      (node (ref "JP13") (pin "1") (pinfunction "1_1") (pintype "passive"))
      (node (ref "JP3") (pin "1") (pinfunction "1_1") (pintype "passive"))
      (node (ref "R44") (pin "2") (pinfunction "2_2") (pintype "passive"))
      (node (ref "R53") (pin "2") (pinfunction "2_2") (pintype "passive"))
      (node (ref "RN4") (pin "1") (pinfunction "1_1") (pintype "passive"))
      (node (ref "RN5") (pin "9") (pinfunction "9_9") (pintype "passive"))
    )
    (net (code "94") (name "Net-(JP14-Pad1)") (class "Default")
      (node (ref "JP14") (pin "1") (pinfunction "1_1") (pintype "passive"))
      (node (ref "JP2") (pin "1") (pinfunction "1_1") (pintype "passive"))
      (node (ref "R35") (pin "2") (pinfunction "2_2") (pintype "passive"))
      (node (ref "R45") (pin "2") (pinfunction "2_2") (pintype "passive"))
      (node (ref "RN1") (pin "1") (pinfunction "1_1") (pintype "passive"))
      (node (ref "RN2") (pin "9") (pinfunction "9_9") (pintype "passive"))
    )
    (net (code "95") (name "Net-(Q1-G)") (class "Default")
      (node (ref "Q1") (pin "1") (pinfunction "G_1") (pintype "passive"))
      (node (ref "R3") (pin "2") (pinfunction "2_2") (pintype "passive"))
    )
    (net (code "96") (name "Net-(Q2-G)") (class "Default")
      (node (ref "Q2") (pin "1") (pinfunction "G_1") (pintype "passive"))
      (node (ref "R4") (pin "2") (pinfunction "2_2") (pintype "passive"))
    )
    (net (code "97") (name "Net-(Q3-G)") (class "Default")
      (node (ref "Q3") (pin "1") (pinfunction "G_1") (pintype "passive"))
      (node (ref "R5") (pin "2") (pinfunction "2_2") (pintype "passive"))
    )
    (net (code "98") (name "Net-(Q4-G)") (class "Default")
      (node (ref "Q4") (pin "1") (pinfunction "G_1") (pintype "passive"))
      (node (ref "R6") (pin "2") (pinfunction "2_2") (pintype "passive"))
    )
    (net (code "99") (name "Net-(Q5-G)") (class "Default")
      (node (ref "Q5") (pin "1") (pinfunction "G_1") (pintype "passive"))
      (node (ref "R7") (pin "2") (pinfunction "2_2") (pintype "passive"))
    )
    (net (code "100") (name "Net-(Q6-G)") (class "Default")
      (node (ref "Q6") (pin "1") (pinfunction "G_1") (pintype "passive"))
      (node (ref "R8") (pin "2") (pinfunction "2_2") (pintype "passive"))
    )
    (net (code "101") (name "Net-(Q7-G)") (class "Default")
      (node (ref "Q7") (pin "1") (pinfunction "G_1") (pintype "passive"))
      (node (ref "R9") (pin "2") (pinfunction "2_2") (pintype "passive"))
    )
    (net (code "102") (name "Net-(Q8-G)") (class "Default")
      (node (ref "Q8") (pin "1") (pinfunction "G_1") (pintype "passive"))
      (node (ref "R10") (pin "2") (pinfunction "2_2") (pintype "passive"))
    )
    (net (code "103") (name "Net-(Q9-G)") (class "Default")
      (node (ref "Q9") (pin "1") (pinfunction "G_1") (pintype "passive"))
      (node (ref "R11") (pin "2") (pinfunction "2_2") (pintype "passive"))
    )
    (net (code "104") (name "Net-(Q10-G)") (class "Default")
      (node (ref "Q10") (pin "1") (pinfunction "G_1") (pintype "passive"))
      (node (ref "R12") (pin "2") (pinfunction "2_2") (pintype "passive"))
    )
    (net (code "105") (name "Net-(Q11-G)") (class "Default")
      (node (ref "Q11") (pin "1") (pinfunction "G_1") (pintype "passive"))
      (node (ref "R13") (pin "2") (pinfunction "2_2") (pintype "passive"))
    )
    (net (code "106") (name "Net-(Q12-G)") (class "Default")
      (node (ref "Q12") (pin "1") (pinfunction "G_1") (pintype "passive"))
      (node (ref "R14") (pin "2") (pinfunction "2_2") (pintype "passive"))
    )
    (net (code "107") (name "Net-(Q13-G)") (class "Default")
      (node (ref "Q13") (pin "1") (pinfunction "G_1") (pintype "passive"))
      (node (ref "R15") (pin "2") (pinfunction "2_2") (pintype "passive"))
    )
    (net (code "108") (name "Net-(Q14-G)") (class "Default")
      (node (ref "Q14") (pin "1") (pinfunction "G_1") (pintype "passive"))
      (node (ref "R16") (pin "2") (pinfunction "2_2") (pintype "passive"))
    )
    (net (code "109") (name "Net-(Q15-G)") (class "Default")
      (node (ref "Q15") (pin "1") (pinfunction "G_1") (pintype "passive"))
      (node (ref "R17") (pin "2") (pinfunction "2_2") (pintype "passive"))
    )
    (net (code "110") (name "Net-(Q16-G)") (class "Default")
      (node (ref "Q16") (pin "1") (pinfunction "G_1") (pintype "passive"))
      (node (ref "R18") (pin "2") (pinfunction "2_2") (pintype "passive"))
    )
    (net (code "111") (name "Net-(RN1B-1)") (class "Default")
      (node (ref "JP14") (pin "2") (pinfunction "2_2") (pintype "passive"))
      (node (ref "JP2") (pin "2") (pinfunction "2_2") (pintype "passive"))
      (node (ref "R34") (pin "2") (pinfunction "2_2") (pintype "passive"))
      (node (ref "R46") (pin "1") (pinfunction "1_1") (pintype "passive"))
      (node (ref "RN1") (pin "2") (pinfunction "1_2") (pintype "passive"))
      (node (ref "RN2") (pin "8") (pinfunction "8_8") (pintype "passive"))
    )
    (net (code "112") (name "Net-(RN1C-1)") (class "Default")
      (node (ref "JP14") (pin "3") (pinfunction "3_3") (pintype "passive"))
      (node (ref "JP2") (pin "3") (pinfunction "3_3") (pintype "passive"))
      (node (ref "R33") (pin "2") (pinfunction "2_2") (pintype "passive"))
      (node (ref "R47") (pin "1") (pinfunction "1_1") (pintype "passive"))
      (node (ref "RN1") (pin "3") (pinfunction "1_3") (pintype "passive"))
      (node (ref "RN2") (pin "7") (pinfunction "7_7") (pintype "passive"))
    )
    (net (code "113") (name "Net-(RN1D-1)") (class "Default")
      (node (ref "JP14") (pin "4") (pinfunction "4_4") (pintype "passive"))
      (node (ref "JP2") (pin "4") (pinfunction "4_4") (pintype "passive"))
      (node (ref "R32") (pin "2") (pinfunction "2_2") (pintype "passive"))
      (node (ref "R48") (pin "1") (pinfunction "1_1") (pintype "passive"))
      (node (ref "RN1") (pin "4") (pinfunction "1_4") (pintype "passive"))
      (node (ref "RN2") (pin "6") (pinfunction "6_6") (pintype "passive"))
    )
    (net (code "114") (name "Net-(RN1E-1)") (class "Default")
      (node (ref "JP14") (pin "7") (pinfunction "7_7") (pintype "passive"))
      (node (ref "JP2") (pin "5") (pinfunction "5_5") (pintype "passive"))
      (node (ref "R31") (pin "2") (pinfunction "2_2") (pintype "passive"))
      (node (ref "R49") (pin "1") (pinfunction "1_1") (pintype "passive"))
      (node (ref "RN1") (pin "5") (pinfunction "1_5") (pintype "passive"))
      (node (ref "RN2") (pin "5") (pinfunction "5_5") (pintype "passive"))
    )
    (net (code "115") (name "Net-(RN1F-1)") (class "Default")
      (node (ref "JP14") (pin "8") (pinfunction "8_8") (pintype "passive"))
      (node (ref "JP2") (pin "6") (pinfunction "6_6") (pintype "passive"))
      (node (ref "R30") (pin "2") (pinfunction "2_2") (pintype "passive"))
      (node (ref "R50") (pin "1") (pinfunction "1_1") (pintype "passive"))
      (node (ref "RN1") (pin "6") (pinfunction "1_6") (pintype "passive"))
      (node (ref "RN2") (pin "4") (pinfunction "4_4") (pintype "passive"))
    )
    (net (code "116") (name "Net-(RN1G-1)") (class "Default")
      (node (ref "JP14") (pin "9") (pinfunction "9_9") (pintype "passive"))
      (node (ref "JP2") (pin "7") (pinfunction "7_7") (pintype "passive"))
      (node (ref "R29") (pin "2") (pinfunction "2_2") (pintype "passive"))
      (node (ref "R51") (pin "1") (pinfunction "1_1") (pintype "passive"))
      (node (ref "RN1") (pin "7") (pinfunction "1_7") (pintype "passive"))
      (node (ref "RN2") (pin "3") (pinfunction "3_3") (pintype "passive"))
    )
    (net (code "117") (name "Net-(RN1H-1)") (class "Default")
      (node (ref "JP14") (pin "10") (pinfunction "10_10") (pintype "passive"))
      (node (ref "JP2") (pin "8") (pinfunction "8_8") (pintype "passive"))
      (node (ref "R28") (pin "2") (pinfunction "2_2") (pintype "passive"))
      (node (ref "R52") (pin "1") (pinfunction "1_1") (pintype "passive"))
      (node (ref "RN1") (pin "8") (pinfunction "1_8") (pintype "passive"))
      (node (ref "RN2") (pin "2") (pinfunction "2_2") (pintype "passive"))
    )
    (net (code "118") (name "Net-(RN4B-1)") (class "Default")
      (node (ref "JP13") (pin "2") (pinfunction "2_2") (pintype "passive"))
      (node (ref "JP3") (pin "2") (pinfunction "2_2") (pintype "passive"))
      (node (ref "R43") (pin "2") (pinfunction "2_2") (pintype "passive"))
      (node (ref "R54") (pin "2") (pinfunction "2_2") (pintype "passive"))
      (node (ref "RN4") (pin "2") (pinfunction "1_2") (pintype "passive"))
      (node (ref "RN5") (pin "8") (pinfunction "8_8") (pintype "passive"))
    )
    (net (code "119") (name "Net-(RN4C-1)") (class "Default")
      (node (ref "JP13") (pin "3") (pinfunction "3_3") (pintype "passive"))
      (node (ref "JP3") (pin "3") (pinfunction "3_3") (pintype "passive"))
      (node (ref "R42") (pin "2") (pinfunction "2_2") (pintype "passive"))
      (node (ref "R55") (pin "2") (pinfunction "2_2") (pintype "passive"))
      (node (ref "RN4") (pin "3") (pinfunction "1_3") (pintype "passive"))
      (node (ref "RN5") (pin "7") (pinfunction "7_7") (pintype "passive"))
    )
    (net (code "120") (name "Net-(RN4D-1)") (class "Default")
      (node (ref "JP13") (pin "4") (pinfunction "4_4") (pintype "passive"))
      (node (ref "JP3") (pin "4") (pinfunction "4_4") (pintype "passive"))
      (node (ref "R41") (pin "2") (pinfunction "2_2") (pintype "passive"))
      (node (ref "R56") (pin "2") (pinfunction "2_2") (pintype "passive"))
      (node (ref "RN4") (pin "4") (pinfunction "1_4") (pintype "passive"))
      (node (ref "RN5") (pin "6") (pinfunction "6_6") (pintype "passive"))
    )
    (net (code "121") (name "Net-(RN4E-1)") (class "Default")
      (node (ref "JP13") (pin "7") (pinfunction "7_7") (pintype "passive"))
      (node (ref "JP3") (pin "5") (pinfunction "5_5") (pintype "passive"))
      (node (ref "R39") (pin "2") (pinfunction "2_2") (pintype "passive"))
      (node (ref "R57") (pin "2") (pinfunction "2_2") (pintype "passive"))
      (node (ref "RN4") (pin "5") (pinfunction "1_5") (pintype "passive"))
      (node (ref "RN5") (pin "5") (pinfunction "5_5") (pintype "passive"))
    )
    (net (code "122") (name "Net-(RN4F-1)") (class "Default")
      (node (ref "JP13") (pin "8") (pinfunction "8_8") (pintype "passive"))
      (node (ref "JP3") (pin "6") (pinfunction "6_6") (pintype "passive"))
      (node (ref "R38") (pin "2") (pinfunction "2_2") (pintype "passive"))
      (node (ref "R58") (pin "2") (pinfunction "2_2") (pintype "passive"))
      (node (ref "RN4") (pin "6") (pinfunction "1_6") (pintype "passive"))
      (node (ref "RN5") (pin "4") (pinfunction "4_4") (pintype "passive"))
    )
    (net (code "123") (name "Net-(RN4G-1)") (class "Default")
      (node (ref "JP13") (pin "9") (pinfunction "9_9") (pintype "passive"))
      (node (ref "JP3") (pin "7") (pinfunction "7_7") (pintype "passive"))
      (node (ref "R37") (pin "2") (pinfunction "2_2") (pintype "passive"))
      (node (ref "R59") (pin "2") (pinfunction "2_2") (pintype "passive"))
      (node (ref "RN4") (pin "7") (pinfunction "1_7") (pintype "passive"))
      (node (ref "RN5") (pin "3") (pinfunction "3_3") (pintype "passive"))
    )
    (net (code "124") (name "Net-(RN4H-1)") (class "Default")
      (node (ref "JP13") (pin "10") (pinfunction "10_10") (pintype "passive"))
      (node (ref "JP3") (pin "8") (pinfunction "8_8") (pintype "passive"))
      (node (ref "R36") (pin "2") (pinfunction "2_2") (pintype "passive"))
      (node (ref "R60") (pin "2") (pinfunction "2_2") (pintype "passive"))
      (node (ref "RN4") (pin "8") (pinfunction "1_8") (pintype "passive"))
      (node (ref "RN5") (pin "2") (pinfunction "2_2") (pintype "passive"))
    )
    (net (code "125") (name "Net-(SJ13-1)") (class "Default")
      (node (ref "SJ13") (pin "P$1") (pinfunction "1_P$1") (pintype "passive"))
      (node (ref "U$1") (pin "PB14") (pinfunction "PB14_PB14") (pintype "bidirectional"))
    )
    (net (code "126") (name "Net-(SJ14-1)") (class "Default")
      (node (ref "SJ14") (pin "P$1") (pinfunction "1_P$1") (pintype "passive"))
      (node (ref "U$1") (pin "VIN2") (pinfunction "VIN2_VIN2") (pintype "power_in"))
    )
    (net (code "127") (name "Net-(SJ16-2)") (class "Default")
      (node (ref "JP9") (pin "2") (pinfunction "2_2") (pintype "passive"))
      (node (ref "SJ15") (pin "2") (pinfunction "2_2") (pintype "passive"))
      (node (ref "SJ16") (pin "P$2") (pinfunction "2_P$2") (pintype "passive"))
    )
    (net (code "128") (name "OLAT") (class "Default")
      (node (ref "IC3") (pin "12") (pinfunction "RCK_12") (pintype "input"))
      (node (ref "IC5") (pin "12") (pinfunction "RCK_12") (pintype "input"))
      (node (ref "R21") (pin "1") (pinfunction "1_1") (pintype "passive"))
      (node (ref "U$1") (pin "PA8") (pinfunction "PA8_PA8") (pintype "bidirectional"))
    )
    (net (code "129") (name "SCK") (class "Default")
      (node (ref "IC3") (pin "11") (pinfunction "SCK_11") (pintype "input"))
      (node (ref "IC5") (pin "11") (pinfunction "SCK_11") (pintype "input"))
      (node (ref "JP9") (pin "3") (pinfunction "3_3") (pintype "passive"))
      (node (ref "R19") (pin "1") (pinfunction "1_1") (pintype "passive"))
      (node (ref "U$1") (pin "PB3") (pinfunction "PB3_PB3") (pintype "bidirectional"))
    )
    (net (code "130") (name "SCK2") (class "Default")
      (node (ref "IC1") (pin "7") (pinfunction "CLK_7") (pintype "input"))
      (node (ref "IC4") (pin "7") (pinfunction "CLK_7") (pintype "input"))
      (node (ref "U$1") (pin "PB10") (pinfunction "PB10_PB10") (pintype "bidirectional"))
    )
    (net (code "131") (name "SLNK1") (class "Default")
      (node (ref "IC3") (pin "14") (pinfunction "SER_14") (pintype "input"))
      (node (ref "IC5") (pin "9") (pinfunction "QH*_9") (pintype "tri_state"))
      (node (ref "SJ17") (pin "P$1") (pinfunction "1_P$1") (pintype "passive"))
    )
    (net (code "132") (name "SLNK2") (class "Default")
      (node (ref "IC3") (pin "9") (pinfunction "QH*_9") (pintype "tri_state"))
      (node (ref "SJ16") (pin "P$1") (pinfunction "1_P$1") (pintype "passive"))
    )
    (net (code "133") (name "SLNK3") (class "Default")
      (node (ref "IC1") (pin "13") (pinfunction "QH_13") (pintype "output"))
      (node (ref "IC4") (pin "1") (pinfunction "SER_1") (pintype "input"))
    )
    (net (code "134") (name "SRV1") (class "Default")
      (node (ref "JP7") (pin "2") (pinfunction "2_2") (pintype "passive"))
      (node (ref "R25") (pin "2") (pinfunction "2_2") (pintype "passive"))
      (node (ref "U$1") (pin "PC9") (pinfunction "PC9_PC9") (pintype "bidirectional"))
    )
    (net (code "135") (name "SRV2") (class "Default")
      (node (ref "JP7") (pin "1") (pinfunction "1_1") (pintype "passive"))
      (node (ref "R24") (pin "2") (pinfunction "2_2") (pintype "passive"))
      (node (ref "U$1") (pin "PC7") (pinfunction "PC7_PC7") (pintype "bidirectional"))
    )
    (net (code "136") (name "SRV3") (class "Default")
      (node (ref "JP11") (pin "2") (pinfunction "2_2") (pintype "passive"))
      (node (ref "R26") (pin "2") (pinfunction "2_2") (pintype "passive"))
      (node (ref "U$1") (pin "PC8") (pinfunction "PC8_PC8") (pintype "bidirectional"))
    )
    (net (code "137") (name "SRV4") (class "Default")
      (node (ref "JP11") (pin "1") (pinfunction "1_1") (pintype "passive"))
      (node (ref "R27") (pin "2") (pinfunction "2_2") (pintype "passive"))
      (node (ref "U$1") (pin "PC6") (pinfunction "PC6_PC6") (pintype "bidirectional"))
    )
    (net (code "138") (name "SRV5") (class "Default")
      (node (ref "JP12") (pin "2") (pinfunction "2_2") (pintype "passive"))
      (node (ref "R64") (pin "2") (pinfunction "2_2") (pintype "passive"))
      (node (ref "U$1") (pin "PF1-PH1") (pinfunction "PF1-PH1_PF1-PH1") (pintype "bidirectional"))
    )
    (net (code "139") (name "SRV6") (class "Default")
      (node (ref "JP12") (pin "1") (pinfunction "1_1") (pintype "passive"))
      (node (ref "R65") (pin "2") (pinfunction "2_2") (pintype "passive"))
      (node (ref "U$1") (pin "PA15") (pinfunction "PA15_PA15") (pintype "bidirectional"))
    )
    (net (code "140") (name "SRV7") (class "Default")
      (node (ref "JP16") (pin "2") (pinfunction "2_2") (pintype "passive"))
      (node (ref "R66") (pin "2") (pinfunction "2_2") (pintype "passive"))
      (node (ref "U$1") (pin "PC12") (pinfunction "PC12_PC12") (pintype "bidirectional"))
    )
    (net (code "141") (name "SRV8") (class "Default")
      (node (ref "JP16") (pin "1") (pinfunction "1_1") (pintype "passive"))
      (node (ref "R67") (pin "2") (pinfunction "2_2") (pintype "passive"))
      (node (ref "U$1") (pin "PD2") (pinfunction "PD2_PD2") (pintype "bidirectional"))
    )
    (net (code "142") (name "TIN1") (class "Default")
      (node (ref "IC9") (pin "3") (pinfunction "+IN_3") (pintype "input"))
      (node (ref "U$1") (pin "PB2") (pinfunction "PB2_PB2") (pintype "bidirectional"))
      (node (ref "U$3") (pin "4") (pinfunction "I_4") (pintype "input"))
    )
    (net (code "143") (name "TIN2") (class "Default")
      (node (ref "IC9") (pin "5") (pinfunction "+IN_5") (pintype "input"))
      (node (ref "U$1") (pin "PB1") (pinfunction "PB1_PB1") (pintype "bidirectional"))
      (node (ref "U$2") (pin "2") (pinfunction "I_2") (pintype "input"))
    )
    (net (code "144") (name "TIN3") (class "Default")
      (node (ref "IC9") (pin "10") (pinfunction "+IN_10") (pintype "input"))
      (node (ref "U$1") (pin "PB15") (pinfunction "PB15_PB15") (pintype "bidirectional"))
      (node (ref "U$2") (pin "4") (pinfunction "I_4") (pintype "input"))
    )
    (net (code "145") (name "TIN4") (class "Default")
      (node (ref "IC9") (pin "12") (pinfunction "+IN_12") (pintype "input"))
      (node (ref "U$1") (pin "PB12") (pinfunction "PB12_PB12") (pintype "bidirectional"))
      (node (ref "U$3") (pin "2") (pinfunction "I_2") (pintype "input"))
    )
    (net (code "146") (name "TIN5") (class "Default")
      (node (ref "IC6") (pin "3") (pinfunction "+IN_3") (pintype "input"))
      (node (ref "U$1") (pin "PA4") (pinfunction "PA4_PA4") (pintype "bidirectional"))
      (node (ref "U$5") (pin "4") (pinfunction "I_4") (pintype "input"))
    )
    (net (code "147") (name "TIN6") (class "Default")
      (node (ref "IC6") (pin "5") (pinfunction "+IN_5") (pintype "input"))
      (node (ref "U$1") (pin "PC0") (pinfunction "PC0_PC0") (pintype "bidirectional"))
      (node (ref "U$4") (pin "2") (pinfunction "I_2") (pintype "input"))
    )
    (net (code "148") (name "TIN7") (class "Default")
      (node (ref "IC6") (pin "10") (pinfunction "+IN_10") (pintype "input"))
      (node (ref "U$1") (pin "PC3") (pinfunction "PC3_PC3") (pintype "bidirectional"))
      (node (ref "U$4") (pin "4") (pinfunction "I_4") (pintype "input"))
    )
    (net (code "149") (name "TIN8") (class "Default")
      (node (ref "IC6") (pin "12") (pinfunction "+IN_12") (pintype "input"))
      (node (ref "U$1") (pin "PA0") (pinfunction "PA0_PA0") (pintype "bidirectional"))
      (node (ref "U$5") (pin "2") (pinfunction "I_2") (pintype "input"))
    )
    (net (code "150") (name "V+") (class "Default")
      (node (ref "AP1509") (pin "3") (pinfunction "FB_3") (pintype "bidirectional"))
      (node (ref "C1") (pin "1") (pinfunction "1_1") (pintype "passive"))
      (node (ref "C2") (pin "+") (pinfunction "+_+") (pintype "passive"))
      (node (ref "IC10") (pin "1") (pinfunction "FB_1") (pintype "input"))
      (node (ref "L1") (pin "1") (pinfunction "1_1") (pintype "passive"))
      (node (ref "U$1") (pin "E5V") (pinfunction "E5V_E5V") (pintype "power_in"))
    )
    (net (code "151") (name "unconnected-(H1-MOUNT-PadB3,3)") (class "Default")
      (node (ref "H1") (pin "B3,3") (pinfunction "MOUNT_B3,3") (pintype "passive"))
    )
    (net (code "152") (name "unconnected-(H2-MOUNT-PadB3,3)") (class "Default")
      (node (ref "H2") (pin "B3,3") (pinfunction "MOUNT_B3,3") (pintype "passive"))
    )
    (net (code "153") (name "unconnected-(H3-MOUNT-PadB3,3)") (class "Default")
      (node (ref "H3") (pin "B3,3") (pinfunction "MOUNT_B3,3") (pintype "passive"))
    )
    (net (code "154") (name "unconnected-(H4-MOUNT-PadB3,3)") (class "Default")
      (node (ref "H4") (pin "B3,3") (pinfunction "MOUNT_B3,3") (pintype "passive"))
    )
    (net (code "155") (name "unconnected-(J3-Pad2)") (class "Default")
      (node (ref "J3") (pin "2") (pinfunction "2_2") (pintype "passive"))
    )
    (net (code "156") (name "unconnected-(U$1-PadBOOT0)") (class "Default")
      (node (ref "U$1") (pin "BOOT0") (pinfunction "BOOT0_BOOT0") (pintype "bidirectional"))
    )
    (net (code "157") (name "unconnected-(U$1-PadIOREF2)") (class "Default")
      (node (ref "U$1") (pin "IOREF2") (pinfunction "IOREF2_IOREF2") (pintype "input"))
    )
    (net (code "158") (name "unconnected-(U$1-PadNC1-PF7)") (class "Default")
      (node (ref "U$1") (pin "NC1-PF7") (pinfunction "NC1-PF7_NC1-PF7") (pintype "bidirectional"))
    )
    (net (code "159") (name "unconnected-(U$1-PadNC2-PF6)") (class "Default")
      (node (ref "U$1") (pin "NC2-PF6") (pinfunction "NC2-PF6_NC2-PF6") (pintype "bidirectional"))
    )
    (net (code "160") (name "unconnected-(U$1-PadNC3)") (class "Default")
      (node (ref "U$1") (pin "NC3") (pinfunction "NC3_NC3") (pintype "no_connect"))
    )
    (net (code "161") (name "unconnected-(U$1-PadNC4)") (class "Default")
      (node (ref "U$1") (pin "NC4") (pinfunction "NC4_NC4") (pintype "no_connect"))
    )
    (net (code "162") (name "unconnected-(U$1-PadNC5-PD8)") (class "Default")
      (node (ref "U$1") (pin "NC5-PD8") (pinfunction "NC5-PD8_NC5-PD8") (pintype "bidirectional"))
    )
    (net (code "163") (name "unconnected-(U$1-PadNC6-PB11)") (class "Default")
      (node (ref "U$1") (pin "NC6-PB11") (pinfunction "NC6-PB11_NC6-PB11") (pintype "no_connect"))
    )
    (net (code "164") (name "unconnected-(U$1-PadNC7-PF5)") (class "Default")
      (node (ref "U$1") (pin "NC7-PF5") (pinfunction "NC7-PF5_NC7-PF5") (pintype "bidirectional"))
    )
    (net (code "165") (name "unconnected-(U$1-PadNC8-PF4)") (class "Default")
      (node (ref "U$1") (pin "NC8-PF4") (pinfunction "NC8-PF4_NC8-PF4") (pintype "bidirectional"))
    )
    (net (code "166") (name "unconnected-(U$1-PadNRESET)") (class "Default")
      (node (ref "U$1") (pin "NRESET") (pinfunction "NRESET_NRESET") (pintype "input"))
    )
    (net (code "167") (name "unconnected-(U$1-PadPA1)") (class "Default")
      (node (ref "U$1") (pin "PA1") (pinfunction "PA1_PA1") (pintype "bidirectional"))
    )
    (net (code "168") (name "unconnected-(U$1-PadPA2)") (class "Default")
      (node (ref "U$1") (pin "PA2") (pinfunction "PA2_PA2") (pintype "bidirectional"))
    )
    (net (code "169") (name "unconnected-(U$1-PadPA3)") (class "Default")
      (node (ref "U$1") (pin "PA3") (pinfunction "PA3_PA3") (pintype "bidirectional"))
    )
    (net (code "170") (name "unconnected-(U$1-PadPA5)") (class "Default")
      (node (ref "U$1") (pin "PA5") (pinfunction "PA5_PA5") (pintype "bidirectional"))
    )
    (net (code "171") (name "unconnected-(U$1-PadPA7)") (class "Default")
      (node (ref "U$1") (pin "PA7") (pinfunction "PA7_PA7") (pintype "bidirectional"))
    )
    (net (code "172") (name "unconnected-(U$1-PadPA9)") (class "Default")
      (node (ref "U$1") (pin "PA9") (pinfunction "PA9_PA9") (pintype "bidirectional"))
    )
    (net (code "173") (name "unconnected-(U$1-PadPA10)") (class "Default")
      (node (ref "U$1") (pin "PA10") (pinfunction "PA10_PA10") (pintype "bidirectional"))
    )
    (net (code "174") (name "unconnected-(U$1-PadPA11)") (class "Default")
      (node (ref "U$1") (pin "PA11") (pinfunction "PA11_PA11") (pintype "bidirectional"))
    )
    (net (code "175") (name "unconnected-(U$1-PadPA12)") (class "Default")
      (node (ref "U$1") (pin "PA12") (pinfunction "PA12_PA12") (pintype "bidirectional"))
    )
    (net (code "176") (name "unconnected-(U$1-PadPA13)") (class "Default")
      (node (ref "U$1") (pin "PA13") (pinfunction "PA13_PA13") (pintype "bidirectional"))
    )
    (net (code "177") (name "unconnected-(U$1-PadPA14)") (class "Default")
      (node (ref "U$1") (pin "PA14") (pinfunction "PA14_PA14") (pintype "bidirectional"))
    )
    (net (code "178") (name "unconnected-(U$1-PadPB0)") (class "Default")
      (node (ref "U$1") (pin "PB0") (pinfunction "PB0_PB0") (pintype "bidirectional"))
    )
    (net (code "179") (name "unconnected-(U$1-PadPB13)") (class "Default")
      (node (ref "U$1") (pin "PB13") (pinfunction "PB13_PB13") (pintype "bidirectional"))
    )
    (net (code "180") (name "unconnected-(U$1-PadPC1)") (class "Default")
      (node (ref "U$1") (pin "PC1") (pinfunction "PC1_PC1") (pintype "bidirectional"))
    )
    (net (code "181") (name "unconnected-(U$1-PadPC4)") (class "Default")
      (node (ref "U$1") (pin "PC4") (pinfunction "PC4_PC4") (pintype "bidirectional"))
    )
    (net (code "182") (name "unconnected-(U$1-PadPC5)") (class "Default")
      (node (ref "U$1") (pin "PC5") (pinfunction "PC5_PC5") (pintype "bidirectional"))
    )
    (net (code "183") (name "unconnected-(U$1-PadPC13)") (class "Default")
      (node (ref "U$1") (pin "PC13") (pinfunction "PC13_PC13") (pintype "bidirectional"))
    )
    (net (code "184") (name "unconnected-(U$1-PadPC14)") (class "Default")
      (node (ref "U$1") (pin "PC14") (pinfunction "PC14_PC14") (pintype "bidirectional"))
    )
    (net (code "185") (name "unconnected-(U$1-PadPC15)") (class "Default")
      (node (ref "U$1") (pin "PC15") (pinfunction "PC15_PC15") (pintype "bidirectional"))
    )
    (net (code "186") (name "unconnected-(U$1-PadPF0-PH0)") (class "Default")
      (node (ref "U$1") (pin "PF0-PH0") (pinfunction "PF0-PH0_PF0-PH0") (pintype "bidirectional"))
    )
  )
)
